# mdcu.net
KiCad netlist of a schematic drawn in Altium Designer
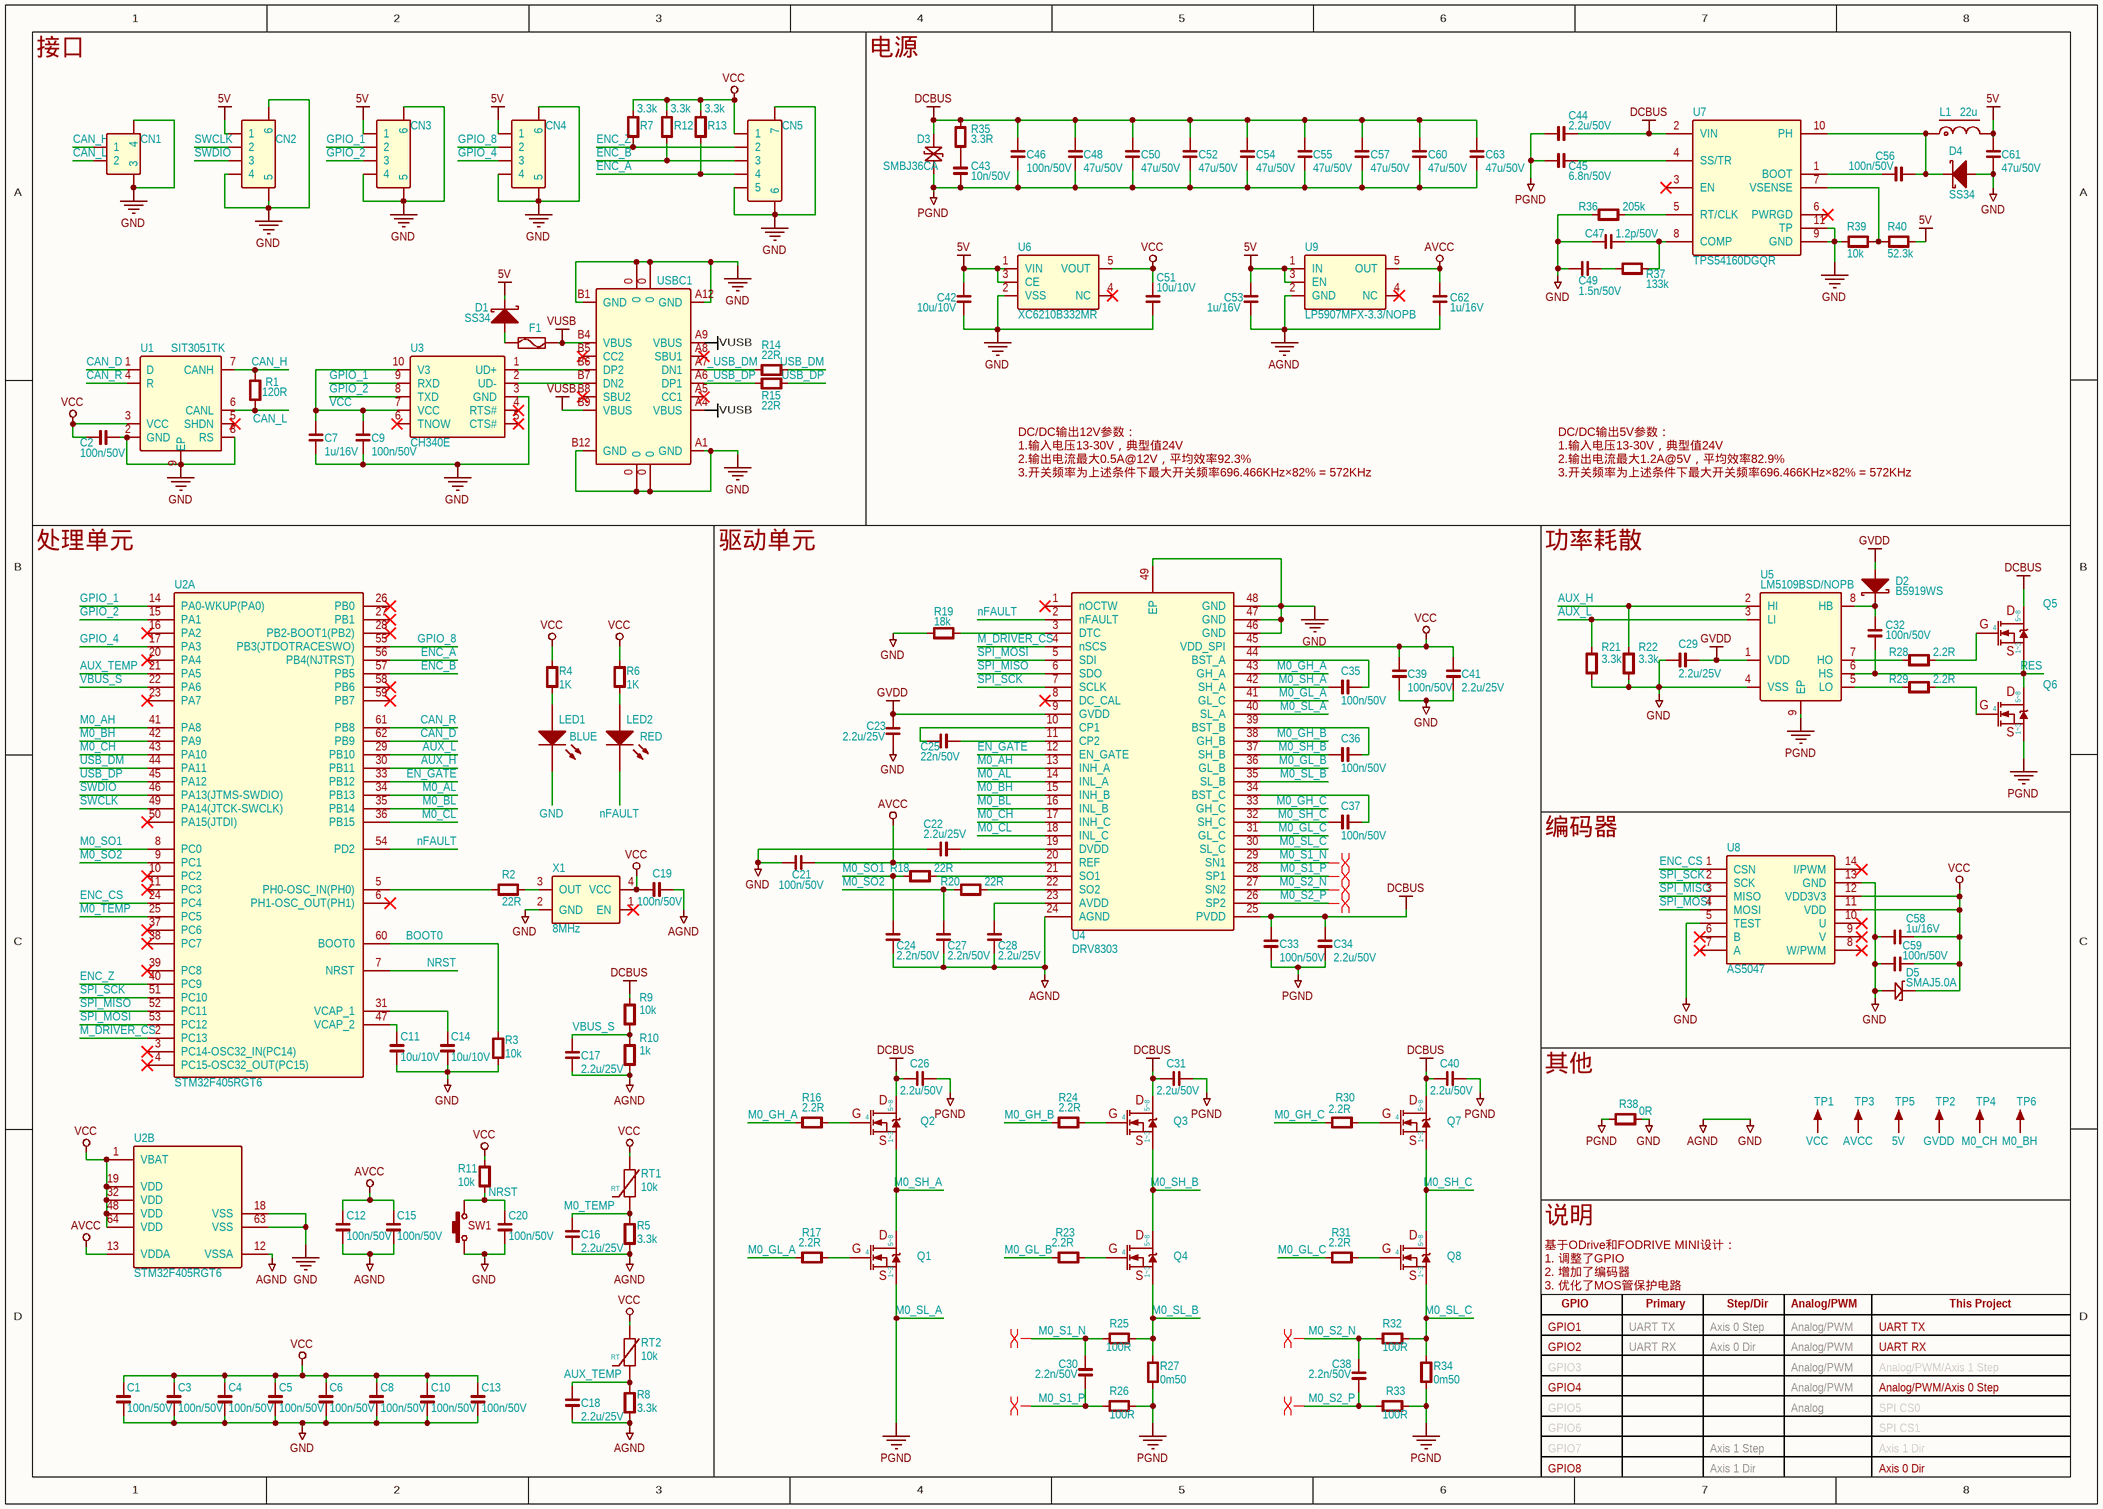
[diagram p0: mdcu.schdoc]

(export (version "E")
  (design (tool "Eeschema 10.0.6"))
  (components
    (comp (ref "C1")
      (value "100n/50V")
      (footprint "C0402_M")
      (description "贴片电容/MLCC电容")
      (libsource (lib "0.1 - 电阻-电容-电感-晶振-晶体-磁珠-电位器-法拉电容-馈通电容") (part "C"))
    )
    (comp (ref "C2")
      (value "100n/50V")
      (footprint "C0402_M")
      (description "贴片电容/MLCC电容")
      (libsource (lib "0.1 - 电阻-电容-电感-晶振-晶体-磁珠-电位器-法拉电容-馈通电容") (part "C"))
    )
    (comp (ref "C3")
      (value "100n/50V")
      (footprint "C0402_M")
      (description "贴片电容/MLCC电容")
      (libsource (lib "0.1 - 电阻-电容-电感-晶振-晶体-磁珠-电位器-法拉电容-馈通电容") (part "C"))
    )
    (comp (ref "C4")
      (value "100n/50V")
      (footprint "C0402_M")
      (description "贴片电容/MLCC电容")
      (libsource (lib "0.1 - 电阻-电容-电感-晶振-晶体-磁珠-电位器-法拉电容-馈通电容") (part "C"))
    )
    (comp (ref "C5")
      (value "100n/50V")
      (footprint "C0402_M")
      (description "贴片电容/MLCC电容")
      (libsource (lib "0.1 - 电阻-电容-电感-晶振-晶体-磁珠-电位器-法拉电容-馈通电容") (part "C"))
    )
    (comp (ref "C6")
      (value "100n/50V")
      (footprint "C0402_M")
      (description "贴片电容/MLCC电容")
      (libsource (lib "0.1 - 电阻-电容-电感-晶振-晶体-磁珠-电位器-法拉电容-馈通电容") (part "C"))
    )
    (comp (ref "C7")
      (value "1u/16V")
      (footprint "C0402_M")
      (description "贴片电容/MLCC电容")
      (libsource (lib "0.1 - 电阻-电容-电感-晶振-晶体-磁珠-电位器-法拉电容-馈通电容") (part "C"))
    )
    (comp (ref "C8")
      (value "100n/50V")
      (footprint "C0402_M")
      (description "贴片电容/MLCC电容")
      (libsource (lib "0.1 - 电阻-电容-电感-晶振-晶体-磁珠-电位器-法拉电容-馈通电容") (part "C"))
    )
    (comp (ref "C9")
      (value "100n/50V")
      (footprint "C0402_M")
      (description "贴片电容/MLCC电容")
      (libsource (lib "0.1 - 电阻-电容-电感-晶振-晶体-磁珠-电位器-法拉电容-馈通电容") (part "C"))
    )
    (comp (ref "C10")
      (value "100n/50V")
      (footprint "C0402_M")
      (description "贴片电容/MLCC电容")
      (libsource (lib "0.1 - 电阻-电容-电感-晶振-晶体-磁珠-电位器-法拉电容-馈通电容") (part "C"))
    )
    (comp (ref "C11")
      (value "10u/10V")
      (footprint "C0402_M")
      (description "贴片电容/MLCC电容")
      (libsource (lib "0.1 - 电阻-电容-电感-晶振-晶体-磁珠-电位器-法拉电容-馈通电容") (part "C"))
    )
    (comp (ref "C12")
      (value "100n/50V")
      (footprint "C0402_M")
      (description "贴片电容/MLCC电容")
      (libsource (lib "0.1 - 电阻-电容-电感-晶振-晶体-磁珠-电位器-法拉电容-馈通电容") (part "C"))
    )
    (comp (ref "C13")
      (value "100n/50V")
      (footprint "C0402_M")
      (description "贴片电容/MLCC电容")
      (libsource (lib "0.1 - 电阻-电容-电感-晶振-晶体-磁珠-电位器-法拉电容-馈通电容") (part "C"))
    )
    (comp (ref "C14")
      (value "10u/10V")
      (footprint "C0402_M")
      (description "贴片电容/MLCC电容")
      (libsource (lib "0.1 - 电阻-电容-电感-晶振-晶体-磁珠-电位器-法拉电容-馈通电容") (part "C"))
    )
    (comp (ref "C15")
      (value "100n/50V")
      (footprint "C0402_M")
      (description "贴片电容/MLCC电容")
      (libsource (lib "0.1 - 电阻-电容-电感-晶振-晶体-磁珠-电位器-法拉电容-馈通电容") (part "C"))
    )
    (comp (ref "C16")
      (value "2.2u/25V")
      (footprint "C0402_M")
      (description "贴片电容/MLCC电容")
      (libsource (lib "0.1 - 电阻-电容-电感-晶振-晶体-磁珠-电位器-法拉电容-馈通电容") (part "C"))
    )
    (comp (ref "C17")
      (value "2.2u/25V")
      (footprint "C0402_M")
      (description "贴片电容/MLCC电容")
      (libsource (lib "0.1 - 电阻-电容-电感-晶振-晶体-磁珠-电位器-法拉电容-馈通电容") (part "C"))
    )
    (comp (ref "C18")
      (value "2.2u/25V")
      (footprint "C0402_M")
      (description "贴片电容/MLCC电容")
      (libsource (lib "0.1 - 电阻-电容-电感-晶振-晶体-磁珠-电位器-法拉电容-馈通电容") (part "C"))
    )
    (comp (ref "C19")
      (value "100n/50V")
      (footprint "C0402_M")
      (description "贴片电容/MLCC电容")
      (libsource (lib "0.1 - 电阻-电容-电感-晶振-晶体-磁珠-电位器-法拉电容-馈通电容") (part "C"))
    )
    (comp (ref "C20")
      (value "100n/50V")
      (footprint "C0402_M")
      (description "贴片电容/MLCC电容")
      (libsource (lib "0.1 - 电阻-电容-电感-晶振-晶体-磁珠-电位器-法拉电容-馈通电容") (part "C"))
    )
    (comp (ref "C21")
      (value "100n/50V")
      (footprint "C0402_M")
      (description "贴片电容/MLCC电容")
      (libsource (lib "0.1 - 电阻-电容-电感-晶振-晶体-磁珠-电位器-法拉电容-馈通电容") (part "C"))
    )
    (comp (ref "C22")
      (value "2.2u/25V")
      (footprint "C0402_M")
      (description "贴片电容/MLCC电容")
      (libsource (lib "0.1 - 电阻-电容-电感-晶振-晶体-磁珠-电位器-法拉电容-馈通电容") (part "C"))
    )
    (comp (ref "C23")
      (value "2.2u/25V")
      (footprint "C0402_M")
      (description "贴片电容/MLCC电容")
      (libsource (lib "0.1 - 电阻-电容-电感-晶振-晶体-磁珠-电位器-法拉电容-馈通电容") (part "C"))
    )
    (comp (ref "C24")
      (value "2.2n/50V")
      (footprint "C0402_M")
      (description "贴片电容/MLCC电容")
      (libsource (lib "0.1 - 电阻-电容-电感-晶振-晶体-磁珠-电位器-法拉电容-馈通电容") (part "C"))
    )
    (comp (ref "C25")
      (value "22n/50V")
      (footprint "C0402_M")
      (description "贴片电容/MLCC电容")
      (libsource (lib "0.1 - 电阻-电容-电感-晶振-晶体-磁珠-电位器-法拉电容-馈通电容") (part "C"))
    )
    (comp (ref "C26")
      (value "2.2u/50V")
      (footprint "C0603_M")
      (description "贴片电容/MLCC电容")
      (libsource (lib "0.1 - 电阻-电容-电感-晶振-晶体-磁珠-电位器-法拉电容-馈通电容") (part "C"))
    )
    (comp (ref "C27")
      (value "2.2n/50V")
      (footprint "C0402_M")
      (description "贴片电容/MLCC电容")
      (libsource (lib "0.1 - 电阻-电容-电感-晶振-晶体-磁珠-电位器-法拉电容-馈通电容") (part "C"))
    )
    (comp (ref "C28")
      (value "2.2u/25V")
      (footprint "C0402_M")
      (description "贴片电容/MLCC电容")
      (libsource (lib "0.1 - 电阻-电容-电感-晶振-晶体-磁珠-电位器-法拉电容-馈通电容") (part "C"))
    )
    (comp (ref "C29")
      (value "2.2u/25V")
      (footprint "C0402_M")
      (description "贴片电容/MLCC电容")
      (libsource (lib "0.1 - 电阻-电容-电感-晶振-晶体-磁珠-电位器-法拉电容-馈通电容") (part "C"))
    )
    (comp (ref "C30")
      (value "2.2n/50V")
      (footprint "C0402_M")
      (description "贴片电容/MLCC电容")
      (libsource (lib "0.1 - 电阻-电容-电感-晶振-晶体-磁珠-电位器-法拉电容-馈通电容") (part "C"))
    )
    (comp (ref "C31")
      (value "2.2u/50V")
      (footprint "C0603_M")
      (description "贴片电容/MLCC电容")
      (libsource (lib "0.1 - 电阻-电容-电感-晶振-晶体-磁珠-电位器-法拉电容-馈通电容") (part "C"))
    )
    (comp (ref "C32")
      (value "100n/50V")
      (footprint "C0402_M")
      (description "贴片电容/MLCC电容")
      (libsource (lib "0.1 - 电阻-电容-电感-晶振-晶体-磁珠-电位器-法拉电容-馈通电容") (part "C"))
    )
    (comp (ref "C33")
      (value "100n/50V")
      (footprint "C0402_M")
      (description "贴片电容/MLCC电容")
      (libsource (lib "0.1 - 电阻-电容-电感-晶振-晶体-磁珠-电位器-法拉电容-馈通电容") (part "C"))
    )
    (comp (ref "C34")
      (value "2.2u/50V")
      (footprint "C0603_M")
      (description "贴片电容/MLCC电容")
      (libsource (lib "0.1 - 电阻-电容-电感-晶振-晶体-磁珠-电位器-法拉电容-馈通电容") (part "C"))
    )
    (comp (ref "C35")
      (value "100n/50V")
      (footprint "C0402_M")
      (description "贴片电容/MLCC电容")
      (libsource (lib "0.1 - 电阻-电容-电感-晶振-晶体-磁珠-电位器-法拉电容-馈通电容") (part "C"))
    )
    (comp (ref "C36")
      (value "100n/50V")
      (footprint "C0402_M")
      (description "贴片电容/MLCC电容")
      (libsource (lib "0.1 - 电阻-电容-电感-晶振-晶体-磁珠-电位器-法拉电容-馈通电容") (part "C"))
    )
    (comp (ref "C37")
      (value "100n/50V")
      (footprint "C0402_M")
      (description "贴片电容/MLCC电容")
      (libsource (lib "0.1 - 电阻-电容-电感-晶振-晶体-磁珠-电位器-法拉电容-馈通电容") (part "C"))
    )
    (comp (ref "C38")
      (value "2.2n/50V")
      (footprint "C0402_M")
      (description "贴片电容/MLCC电容")
      (libsource (lib "0.1 - 电阻-电容-电感-晶振-晶体-磁珠-电位器-法拉电容-馈通电容") (part "C"))
    )
    (comp (ref "C39")
      (value "100n/50V")
      (footprint "C0402_M")
      (description "贴片电容/MLCC电容")
      (libsource (lib "0.1 - 电阻-电容-电感-晶振-晶体-磁珠-电位器-法拉电容-馈通电容") (part "C"))
    )
    (comp (ref "C40")
      (value "2.2u/50V")
      (footprint "C0603_M")
      (description "贴片电容/MLCC电容")
      (libsource (lib "0.1 - 电阻-电容-电感-晶振-晶体-磁珠-电位器-法拉电容-馈通电容") (part "C"))
    )
    (comp (ref "C41")
      (value "2.2u/25V")
      (footprint "C0402_M")
      (description "贴片电容/MLCC电容")
      (libsource (lib "0.1 - 电阻-电容-电感-晶振-晶体-磁珠-电位器-法拉电容-馈通电容") (part "C"))
    )
    (comp (ref "C42")
      (value "10u/10V")
      (footprint "C0402_M")
      (description "贴片电容/MLCC电容")
      (libsource (lib "0.1 - 电阻-电容-电感-晶振-晶体-磁珠-电位器-法拉电容-馈通电容") (part "C"))
    )
    (comp (ref "C43")
      (value "10n/50V")
      (footprint "C0402_M")
      (description "贴片电容/MLCC电容")
      (libsource (lib "0.1 - 电阻-电容-电感-晶振-晶体-磁珠-电位器-法拉电容-馈通电容") (part "C"))
    )
    (comp (ref "C44")
      (value "2.2u/50V")
      (footprint "C0603_M")
      (description "贴片电容/MLCC电容")
      (libsource (lib "0.1 - 电阻-电容-电感-晶振-晶体-磁珠-电位器-法拉电容-馈通电容") (part "C"))
    )
    (comp (ref "C45")
      (value "6.8n/50V")
      (footprint "C0402_M")
      (description "贴片电容/MLCC电容")
      (libsource (lib "0.1 - 电阻-电容-电感-晶振-晶体-磁珠-电位器-法拉电容-馈通电容") (part "C"))
    )
    (comp (ref "C46")
      (value "100n/50V")
      (footprint "C0402_M")
      (description "贴片电容/MLCC电容")
      (libsource (lib "0.1 - 电阻-电容-电感-晶振-晶体-磁珠-电位器-法拉电容-馈通电容") (part "C"))
    )
    (comp (ref "C47")
      (value "1.2p/50V")
      (footprint "C0402_M")
      (description "贴片电容/MLCC电容")
      (libsource (lib "0.1 - 电阻-电容-电感-晶振-晶体-磁珠-电位器-法拉电容-馈通电容") (part "C"))
    )
    (comp (ref "C48")
      (value "47u/50V")
      (footprint "C1812_M")
      (description "贴片电容/MLCC电容")
      (libsource (lib "0.1 - 电阻-电容-电感-晶振-晶体-磁珠-电位器-法拉电容-馈通电容") (part "C"))
    )
    (comp (ref "C49")
      (value "1.5n/50V")
      (footprint "C0402_M")
      (description "贴片电容/MLCC电容")
      (libsource (lib "0.1 - 电阻-电容-电感-晶振-晶体-磁珠-电位器-法拉电容-馈通电容") (part "C"))
    )
    (comp (ref "C50")
      (value "47u/50V")
      (footprint "C1812_M")
      (description "贴片电容/MLCC电容")
      (libsource (lib "0.1 - 电阻-电容-电感-晶振-晶体-磁珠-电位器-法拉电容-馈通电容") (part "C"))
    )
    (comp (ref "C51")
      (value "10u/10V")
      (footprint "C0402_M")
      (description "贴片电容/MLCC电容")
      (libsource (lib "0.1 - 电阻-电容-电感-晶振-晶体-磁珠-电位器-法拉电容-馈通电容") (part "C"))
    )
    (comp (ref "C52")
      (value "47u/50V")
      (footprint "C1812_M")
      (description "贴片电容/MLCC电容")
      (libsource (lib "0.1 - 电阻-电容-电感-晶振-晶体-磁珠-电位器-法拉电容-馈通电容") (part "C"))
    )
    (comp (ref "C53")
      (value "1u/16V")
      (footprint "C0402_M")
      (description "贴片电容/MLCC电容")
      (libsource (lib "0.1 - 电阻-电容-电感-晶振-晶体-磁珠-电位器-法拉电容-馈通电容") (part "C"))
    )
    (comp (ref "C54")
      (value "47u/50V")
      (footprint "C1812_M")
      (description "贴片电容/MLCC电容")
      (libsource (lib "0.1 - 电阻-电容-电感-晶振-晶体-磁珠-电位器-法拉电容-馈通电容") (part "C"))
    )
    (comp (ref "C55")
      (value "47u/50V")
      (footprint "C1812_M")
      (description "贴片电容/MLCC电容")
      (libsource (lib "0.1 - 电阻-电容-电感-晶振-晶体-磁珠-电位器-法拉电容-馈通电容") (part "C"))
    )
    (comp (ref "C56")
      (value "100n/50V")
      (footprint "C0402_M")
      (description "贴片电容/MLCC电容")
      (libsource (lib "0.1 - 电阻-电容-电感-晶振-晶体-磁珠-电位器-法拉电容-馈通电容") (part "C"))
    )
    (comp (ref "C57")
      (value "47u/50V")
      (footprint "C1812_M")
      (description "贴片电容/MLCC电容")
      (libsource (lib "0.1 - 电阻-电容-电感-晶振-晶体-磁珠-电位器-法拉电容-馈通电容") (part "C"))
    )
    (comp (ref "C58")
      (value "1u/16V")
      (footprint "C0402_M")
      (description "贴片电容/MLCC电容")
      (libsource (lib "0.1 - 电阻-电容-电感-晶振-晶体-磁珠-电位器-法拉电容-馈通电容") (part "C"))
    )
    (comp (ref "C59")
      (value "100n/50V")
      (footprint "C0402_M")
      (description "贴片电容/MLCC电容")
      (libsource (lib "0.1 - 电阻-电容-电感-晶振-晶体-磁珠-电位器-法拉电容-馈通电容") (part "C"))
    )
    (comp (ref "C60")
      (value "47u/50V")
      (footprint "C1812_M")
      (description "贴片电容/MLCC电容")
      (libsource (lib "0.1 - 电阻-电容-电感-晶振-晶体-磁珠-电位器-法拉电容-馈通电容") (part "C"))
    )
    (comp (ref "C61")
      (value "47u/50V")
      (footprint "C1812_M")
      (description "贴片电容/MLCC电容")
      (libsource (lib "0.1 - 电阻-电容-电感-晶振-晶体-磁珠-电位器-法拉电容-馈通电容") (part "C"))
    )
    (comp (ref "C62")
      (value "1u/16V")
      (footprint "C0402_M")
      (description "贴片电容/MLCC电容")
      (libsource (lib "0.1 - 电阻-电容-电感-晶振-晶体-磁珠-电位器-法拉电容-馈通电容") (part "C"))
    )
    (comp (ref "C63")
      (value "47u/50V")
      (footprint "C1812_M")
      (description "贴片电容/MLCC电容")
      (libsource (lib "0.1 - 电阻-电容-电感-晶振-晶体-磁珠-电位器-法拉电容-馈通电容") (part "C"))
    )
    (comp (ref "CN1")
      (value "CON-2P")
      (footprint "SH1.0-WT-2P")
      (description "2P连接器")
      (libsource (lib "5.0 - 1.00mm连接器(FPC1.0_SH1.0_1.0排针排母)") (part "Header 2"))
    )
    (comp (ref "CN2")
      (value "CON-4P")
      (footprint "SH1.0-WT-4P")
      (description "4P连接器")
      (libsource (lib "5.0 - 1.00mm连接器(FPC1.0_SH1.0_1.0排针排母)") (part "Header 4"))
    )
    (comp (ref "CN3")
      (value "CON-4P")
      (footprint "SH1.0-WT-4P")
      (description "4P连接器")
      (libsource (lib "5.0 - 1.00mm连接器(FPC1.0_SH1.0_1.0排针排母)") (part "Header 4"))
    )
    (comp (ref "CN4")
      (value "CON-4P")
      (footprint "SH1.0-WT-4P")
      (description "4P连接器")
      (libsource (lib "5.0 - 1.00mm连接器(FPC1.0_SH1.0_1.0排针排母)") (part "Header 4"))
    )
    (comp (ref "CN5")
      (value "CON-5P")
      (footprint "SH1.0-WT-5P")
      (description "5P连接器")
      (libsource (lib "5.0 - 1.00mm连接器(FPC1.0_SH1.0_1.0排针排母)") (part "Header 5"))
    )
    (comp (ref "D1")
      (value "SS34")
      (footprint "SMA")
      (description "肖特基二极管")
      (libsource (lib "0.2 - 二极管-TVS-ESD-整流桥-放电管") (part "SS34"))
    )
    (comp (ref "D2")
      (value "B5919WS")
      (footprint "SOD-323")
      (description "肖特基二极管")
      (libsource (lib "0.2 - 二极管-TVS-ESD-整流桥-放电管") (part "B5819"))
    )
    (comp (ref "D3")
      (value "SMBJ36CA")
      (footprint "SMB-NS")
      (description "瞬态电压抑制二极管-双向")
      (libsource (lib "0.2 - 二极管-TVS-ESD-整流桥-放电管") (part "DR_CA"))
    )
    (comp (ref "D4")
      (value "SS34")
      (footprint "SMA")
      (description "肖特基二极管")
      (libsource (lib "0.2 - 二极管-TVS-ESD-整流桥-放电管") (part "SS34"))
    )
    (comp (ref "D5")
      (value "SMAJ5.0A")
      (footprint "SMA")
      (description "瞬态电压抑制二极管-单向")
      (libsource (lib "0.2 - 二极管-TVS-ESD-整流桥-放电管") (part "DR"))
    )
    (comp (ref "F1")
      (value "FSMD012-1206-R")
      (footprint "FU 1206")
      (description "PPTC自恢复保险丝")
      (libsource (lib "0.5 - 按键_开关_蜂鸣器_保险丝_电池_测试点_Mark点_铜柱") (part "FU-PPTC"))
    )
    (comp (ref "L1")
      (value "22u")
      (footprint "CDRH73")
      (description "CDRH功率屏蔽电感")
      (libsource (lib "0.1 - 电阻-电容-电感-晶振-晶体-磁珠-电位器-法拉电容-馈通电容") (part "L-CDRH"))
    )
    (comp (ref "LED1")
      (value "BLUE")
      (footprint "LED0603_B")
      (description "贴片LED")
      (libsource (lib "0.3 - LED发光二极管-IR二极管_接收管-光耦") (part "LED"))
    )
    (comp (ref "LED2")
      (value "RED")
      (footprint "LED0603_R")
      (description "贴片LED")
      (libsource (lib "0.3 - LED发光二极管-IR二极管_接收管-光耦") (part "LED"))
    )
    (comp (ref "Q1")
      (value "MOSFET-1N-POWER")
      (footprint "PDFN-8-L6-W5-P1.27-3PAD")
      (description "N沟道功率型场效应管")
      (fields (field (name "MF") "ON Semiconductor") (field (name "MP") "NTMFS4935NT1G"))
      (libsource (lib "0.4 - 三极管-场效应管-可控硅") (part "MOSFET-1N-POWER"))
    )
    (comp (ref "Q2")
      (value "MOSFET-1N-POWER")
      (footprint "PDFN-8-L6-W5-P1.27-3PAD")
      (description "N沟道功率型场效应管")
      (fields (field (name "MF") "ON Semiconductor") (field (name "MP") "NTMFS4935NT1G"))
      (libsource (lib "0.4 - 三极管-场效应管-可控硅") (part "MOSFET-1N-POWER"))
    )
    (comp (ref "Q3")
      (value "MOSFET-1N-POWER")
      (footprint "PDFN-8-L6-W5-P1.27-3PAD")
      (description "N沟道功率型场效应管")
      (fields (field (name "MF") "ON Semiconductor") (field (name "MP") "NTMFS4935NT1G"))
      (libsource (lib "0.4 - 三极管-场效应管-可控硅") (part "MOSFET-1N-POWER"))
    )
    (comp (ref "Q4")
      (value "MOSFET-1N-POWER")
      (footprint "PDFN-8-L6-W5-P1.27-3PAD")
      (description "N沟道功率型场效应管")
      (fields (field (name "MF") "ON Semiconductor") (field (name "MP") "NTMFS4935NT1G"))
      (libsource (lib "0.4 - 三极管-场效应管-可控硅") (part "MOSFET-1N-POWER"))
    )
    (comp (ref "Q5")
      (value "MOSFET-1N-POWER")
      (footprint "PDFN-8-L6-W5-P1.27-3PAD")
      (description "N沟道功率型场效应管")
      (fields (field (name "MF") "ON Semiconductor") (field (name "MP") "NTMFS4935NT1G"))
      (libsource (lib "0.4 - 三极管-场效应管-可控硅") (part "MOSFET-1N-POWER"))
    )
    (comp (ref "Q6")
      (value "MOSFET-1N-POWER")
      (footprint "PDFN-8-L6-W5-P1.27-3PAD")
      (description "N沟道功率型场效应管")
      (fields (field (name "MF") "ON Semiconductor") (field (name "MP") "NTMFS4935NT1G"))
      (libsource (lib "0.4 - 三极管-场效应管-可控硅") (part "MOSFET-1N-POWER"))
    )
    (comp (ref "Q7")
      (value "MOSFET-1N-POWER")
      (footprint "PDFN-8-L6-W5-P1.27-3PAD")
      (description "N沟道功率型场效应管")
      (fields (field (name "MF") "ON Semiconductor") (field (name "MP") "NTMFS4935NT1G"))
      (libsource (lib "0.4 - 三极管-场效应管-可控硅") (part "MOSFET-1N-POWER"))
    )
    (comp (ref "Q8")
      (value "MOSFET-1N-POWER")
      (footprint "PDFN-8-L6-W5-P1.27-3PAD")
      (description "N沟道功率型场效应管")
      (fields (field (name "MF") "ON Semiconductor") (field (name "MP") "NTMFS4935NT1G"))
      (libsource (lib "0.4 - 三极管-场效应管-可控硅") (part "MOSFET-1N-POWER"))
    )
    (comp (ref "R1")
      (value "120R")
      (footprint "R0402_M")
      (description "贴片电阻")
      (libsource (lib "0.1 - 电阻-电容-电感-晶振-晶体-磁珠-电位器-法拉电容-馈通电容") (part "R"))
    )
    (comp (ref "R2")
      (value "22R")
      (footprint "R0402_M")
      (description "贴片电阻")
      (libsource (lib "0.1 - 电阻-电容-电感-晶振-晶体-磁珠-电位器-法拉电容-馈通电容") (part "R"))
    )
    (comp (ref "R3")
      (value "10k")
      (footprint "R0402_M")
      (description "贴片电阻")
      (libsource (lib "0.1 - 电阻-电容-电感-晶振-晶体-磁珠-电位器-法拉电容-馈通电容") (part "R"))
    )
    (comp (ref "R4")
      (value "1K")
      (footprint "R0402_M")
      (description "贴片电阻")
      (libsource (lib "0.1 - 电阻-电容-电感-晶振-晶体-磁珠-电位器-法拉电容-馈通电容") (part "R"))
    )
    (comp (ref "R5")
      (value "3.3k")
      (footprint "R0402_M")
      (description "贴片电阻")
      (libsource (lib "0.1 - 电阻-电容-电感-晶振-晶体-磁珠-电位器-法拉电容-馈通电容") (part "R"))
    )
    (comp (ref "R6")
      (value "1K")
      (footprint "R0402_M")
      (description "贴片电阻")
      (libsource (lib "0.1 - 电阻-电容-电感-晶振-晶体-磁珠-电位器-法拉电容-馈通电容") (part "R"))
    )
    (comp (ref "R7")
      (value "3.3k")
      (footprint "R0402_M")
      (description "贴片电阻")
      (libsource (lib "0.1 - 电阻-电容-电感-晶振-晶体-磁珠-电位器-法拉电容-馈通电容") (part "R"))
    )
    (comp (ref "R8")
      (value "3.3k")
      (footprint "R0402_M")
      (description "贴片电阻")
      (libsource (lib "0.1 - 电阻-电容-电感-晶振-晶体-磁珠-电位器-法拉电容-馈通电容") (part "R"))
    )
    (comp (ref "R9")
      (value "10k")
      (footprint "R0402_M")
      (description "贴片电阻")
      (libsource (lib "0.1 - 电阻-电容-电感-晶振-晶体-磁珠-电位器-法拉电容-馈通电容") (part "R"))
    )
    (comp (ref "R10")
      (value "1k")
      (footprint "R0402_M")
      (description "贴片电阻")
      (libsource (lib "0.1 - 电阻-电容-电感-晶振-晶体-磁珠-电位器-法拉电容-馈通电容") (part "R"))
    )
    (comp (ref "R11")
      (value "10k")
      (footprint "R0402_M")
      (description "贴片电阻")
      (libsource (lib "0.1 - 电阻-电容-电感-晶振-晶体-磁珠-电位器-法拉电容-馈通电容") (part "R"))
    )
    (comp (ref "R12")
      (value "3.3k")
      (footprint "R0402_M")
      (description "贴片电阻")
      (libsource (lib "0.1 - 电阻-电容-电感-晶振-晶体-磁珠-电位器-法拉电容-馈通电容") (part "R"))
    )
    (comp (ref "R13")
      (value "3.3k")
      (footprint "R0402_M")
      (description "贴片电阻")
      (libsource (lib "0.1 - 电阻-电容-电感-晶振-晶体-磁珠-电位器-法拉电容-馈通电容") (part "R"))
    )
    (comp (ref "R14")
      (value "22R")
      (footprint "R0402_M")
      (description "贴片电阻")
      (libsource (lib "0.1 - 电阻-电容-电感-晶振-晶体-磁珠-电位器-法拉电容-馈通电容") (part "R"))
    )
    (comp (ref "R15")
      (value "22R")
      (footprint "R0402_M")
      (description "贴片电阻")
      (libsource (lib "0.1 - 电阻-电容-电感-晶振-晶体-磁珠-电位器-法拉电容-馈通电容") (part "R"))
    )
    (comp (ref "R16")
      (value "2.2R")
      (footprint "R0402_M")
      (description "贴片电阻")
      (libsource (lib "0.1 - 电阻-电容-电感-晶振-晶体-磁珠-电位器-法拉电容-馈通电容") (part "R"))
    )
    (comp (ref "R17")
      (value "2.2R")
      (footprint "R0402_M")
      (description "贴片电阻")
      (libsource (lib "0.1 - 电阻-电容-电感-晶振-晶体-磁珠-电位器-法拉电容-馈通电容") (part "R"))
    )
    (comp (ref "R18")
      (value "22R")
      (footprint "R0402_M")
      (description "贴片电阻")
      (libsource (lib "0.1 - 电阻-电容-电感-晶振-晶体-磁珠-电位器-法拉电容-馈通电容") (part "R"))
    )
    (comp (ref "R19")
      (value "18k")
      (footprint "R0402_M")
      (description "贴片电阻")
      (libsource (lib "0.1 - 电阻-电容-电感-晶振-晶体-磁珠-电位器-法拉电容-馈通电容") (part "R"))
    )
    (comp (ref "R20")
      (value "22R")
      (footprint "R0402_M")
      (description "贴片电阻")
      (libsource (lib "0.1 - 电阻-电容-电感-晶振-晶体-磁珠-电位器-法拉电容-馈通电容") (part "R"))
    )
    (comp (ref "R21")
      (value "3.3k")
      (footprint "R0402_M")
      (description "贴片电阻")
      (libsource (lib "0.1 - 电阻-电容-电感-晶振-晶体-磁珠-电位器-法拉电容-馈通电容") (part "R"))
    )
    (comp (ref "R22")
      (value "3.3k")
      (footprint "R0402_M")
      (description "贴片电阻")
      (libsource (lib "0.1 - 电阻-电容-电感-晶振-晶体-磁珠-电位器-法拉电容-馈通电容") (part "R"))
    )
    (comp (ref "R23")
      (value "2.2R")
      (footprint "R0402_M")
      (description "贴片电阻")
      (libsource (lib "0.1 - 电阻-电容-电感-晶振-晶体-磁珠-电位器-法拉电容-馈通电容") (part "R"))
    )
    (comp (ref "R24")
      (value "2.2R")
      (footprint "R0402_M")
      (description "贴片电阻")
      (libsource (lib "0.1 - 电阻-电容-电感-晶振-晶体-磁珠-电位器-法拉电容-馈通电容") (part "R"))
    )
    (comp (ref "R25")
      (value "100R")
      (footprint "R0402_M")
      (description "贴片电阻")
      (libsource (lib "0.1 - 电阻-电容-电感-晶振-晶体-磁珠-电位器-法拉电容-馈通电容") (part "R"))
    )
    (comp (ref "R26")
      (value "100R")
      (footprint "R0402_M")
      (description "贴片电阻")
      (libsource (lib "0.1 - 电阻-电容-电感-晶振-晶体-磁珠-电位器-法拉电容-馈通电容") (part "R"))
    )
    (comp (ref "R27")
      (value "0m50")
      (footprint "R2512-HP_M")
      (description "贴片精密电阻")
      (libsource (lib "0.1 - 电阻-电容-电感-晶振-晶体-磁珠-电位器-法拉电容-馈通电容") (part "R-High Precision"))
    )
    (comp (ref "R28")
      (value "2.2R")
      (footprint "R0402_M")
      (description "贴片电阻")
      (libsource (lib "0.1 - 电阻-电容-电感-晶振-晶体-磁珠-电位器-法拉电容-馈通电容") (part "R"))
    )
    (comp (ref "R29")
      (value "2.2R")
      (footprint "R0402_M")
      (description "贴片电阻")
      (libsource (lib "0.1 - 电阻-电容-电感-晶振-晶体-磁珠-电位器-法拉电容-馈通电容") (part "R"))
    )
    (comp (ref "R30")
      (value "2.2R")
      (footprint "R0402_M")
      (description "贴片电阻")
      (libsource (lib "0.1 - 电阻-电容-电感-晶振-晶体-磁珠-电位器-法拉电容-馈通电容") (part "R"))
    )
    (comp (ref "R31")
      (value "2.2R")
      (footprint "R0402_M")
      (description "贴片电阻")
      (libsource (lib "0.1 - 电阻-电容-电感-晶振-晶体-磁珠-电位器-法拉电容-馈通电容") (part "R"))
    )
    (comp (ref "R32")
      (value "100R")
      (footprint "R0402_M")
      (description "贴片电阻")
      (libsource (lib "0.1 - 电阻-电容-电感-晶振-晶体-磁珠-电位器-法拉电容-馈通电容") (part "R"))
    )
    (comp (ref "R33")
      (value "100R")
      (footprint "R0402_M")
      (description "贴片电阻")
      (libsource (lib "0.1 - 电阻-电容-电感-晶振-晶体-磁珠-电位器-法拉电容-馈通电容") (part "R"))
    )
    (comp (ref "R34")
      (value "0m50")
      (footprint "R2512-HP_M")
      (description "贴片精密电阻")
      (libsource (lib "0.1 - 电阻-电容-电感-晶振-晶体-磁珠-电位器-法拉电容-馈通电容") (part "R-High Precision"))
    )
    (comp (ref "R35")
      (value "3.3R")
      (footprint "R0402_M")
      (description "贴片电阻")
      (libsource (lib "0.1 - 电阻-电容-电感-晶振-晶体-磁珠-电位器-法拉电容-馈通电容") (part "R"))
    )
    (comp (ref "R36")
      (value "205k")
      (footprint "R0402_M")
      (description "贴片电阻")
      (libsource (lib "0.1 - 电阻-电容-电感-晶振-晶体-磁珠-电位器-法拉电容-馈通电容") (part "R"))
    )
    (comp (ref "R37")
      (value "133k")
      (footprint "R0402_M")
      (description "贴片电阻")
      (libsource (lib "0.1 - 电阻-电容-电感-晶振-晶体-磁珠-电位器-法拉电容-馈通电容") (part "R"))
    )
    (comp (ref "R38")
      (value "0R")
      (footprint "R0402_M")
      (description "贴片电阻")
      (libsource (lib "0.1 - 电阻-电容-电感-晶振-晶体-磁珠-电位器-法拉电容-馈通电容") (part "R"))
    )
    (comp (ref "R39")
      (value "10k")
      (footprint "R0402_M")
      (description "贴片电阻")
      (libsource (lib "0.1 - 电阻-电容-电感-晶振-晶体-磁珠-电位器-法拉电容-馈通电容") (part "R"))
    )
    (comp (ref "R40")
      (value "52.3k")
      (footprint "R0402_M")
      (description "贴片电阻")
      (libsource (lib "0.1 - 电阻-电容-电感-晶振-晶体-磁珠-电位器-法拉电容-馈通电容") (part "R"))
    )
    (comp (ref "RT1")
      (value "10k")
      (footprint "R0402-HP_M")
      (description "热敏电阻")
      (libsource (lib "0.1 - 电阻-电容-电感-晶振-晶体-磁珠-电位器-法拉电容-馈通电容") (part "RT"))
    )
    (comp (ref "RT2")
      (value "10k")
      (footprint "R0402-HP_M")
      (description "热敏电阻")
      (libsource (lib "0.1 - 电阻-电容-电感-晶振-晶体-磁珠-电位器-法拉电容-馈通电容") (part "RT"))
    )
    (comp (ref "SW1")
      (value "3x6x5")
      (footprint "SW SMD-3*4*2-180")
      (description "微动开关")
      (libsource (lib "0.5 - 按键_开关_蜂鸣器_保险丝_电池_测试点_Mark点_铜柱") (part "SW-PB"))
    )
    (comp (ref "TP1")
      (value "VCC")
      (footprint "TEST 1")
      (description "测试点")
      (libsource (lib "0.5 - 按键_开关_蜂鸣器_保险丝_电池_测试点_Mark点_铜柱") (part "TEST"))
    )
    (comp (ref "TP2")
      (value "GVDD")
      (footprint "TEST 1")
      (description "测试点")
      (libsource (lib "0.5 - 按键_开关_蜂鸣器_保险丝_电池_测试点_Mark点_铜柱") (part "TEST"))
    )
    (comp (ref "TP3")
      (value "AVCC")
      (footprint "TEST 1")
      (description "测试点")
      (libsource (lib "0.5 - 按键_开关_蜂鸣器_保险丝_电池_测试点_Mark点_铜柱") (part "TEST"))
    )
    (comp (ref "TP4")
      (value "M0_CH")
      (footprint "TEST 1")
      (description "测试点")
      (libsource (lib "0.5 - 按键_开关_蜂鸣器_保险丝_电池_测试点_Mark点_铜柱") (part "TEST"))
    )
    (comp (ref "TP5")
      (value "5V")
      (footprint "TEST 1")
      (description "测试点")
      (libsource (lib "0.5 - 按键_开关_蜂鸣器_保险丝_电池_测试点_Mark点_铜柱") (part "TEST"))
    )
    (comp (ref "TP6")
      (value "M0_BH")
      (footprint "TEST 1")
      (description "测试点")
      (libsource (lib "0.5 - 按键_开关_蜂鸣器_保险丝_电池_测试点_Mark点_铜柱") (part "TEST"))
    )
    (comp (ref "U1")
      (value "SIT3051TK")
      (footprint "DFN-8_L3.0-W3.0-P0.65-BL-EP-M")
      (description "CAN芯片")
      (libsource (lib "0.8 - 常见芯片") (part "SIT3051TK"))
    )
    (comp (ref "U2")
      (value "STM32F405RGT6")
      (footprint "TQFP64 10x10_M")
      (fields (field (name "BOM_SUPPLIER PART") "C15742") (field (name "SUBPART_NO") "1"))
      (libsource (lib "2.7 - STM32 F4系列单片机") (part "STM32F405RGT6_V2"))
    )
    (comp (ref "U3")
      (value "CH340E")
      (footprint "MSOP10_L")
      (description "USB转串口芯片，内置时钟")
      (libsource (lib "0.8 - 常见芯片") (part "CH340E"))
    )
    (comp (ref "U4")
      (value "DRV8303")
      (footprint "HTSSOP-48_L12.5-W6.1-P0.50-M")
      (description "三相电机驱动应用的栅极驱动\r\n器")
      (fields (field (name "BOM_SUPPLIER PART") "C91880") (field (name "CONTRIBUTOR") "矛盾聚合体"))
      (libsource (lib "0.8 - 常见芯片") (part "DRV8303"))
    )
    (comp (ref "U5")
      (value "LM5109BSD/NOPB")
      (footprint "WSON-8_L4.0-W4.0-P0.80-TL-EP")
      (description "USB转串口芯片，内置时钟")
      (libsource (lib "0.8 - 常见芯片") (part "LM5109"))
    )
    (comp (ref "U6")
      (value "XC6210B332MR")
      (footprint "SOT23-5L")
      (description "LDO 0.9A/3.3V")
      (libsource (lib "0.7 - 电源类芯片") (part "XC6210"))
    )
    (comp (ref "U7")
      (value "TPS54160DGQR")
      (footprint "MSOP10-L3.0-W3.0-P0.50-EP")
      (description "DC-DC 1.5A/60V 降压转换器")
      (libsource (lib "0.7 - 电源类芯片") (part "TPS54160DGQR"))
    )
    (comp (ref "U8")
      (value "AS5047")
      (footprint "TSSOP14_M")
      (description "AMS公司14位磁编码器")
      (fields (field (name "版权归属") "封装库来自淘宝 ID：黄晶宝石"))
      (libsource (lib "0.8 - 常见芯片") (part "AS5047"))
    )
    (comp (ref "U9")
      (value "LP5907MFX-3.3/NOPB")
      (footprint "SOT23-5L")
      (description "LDO 0.25A/3.3V 90dB@(100Hz),60dB@(100kHz)")
      (libsource (lib "0.7 - 电源类芯片") (part "LP5907"))
    )
    (comp (ref "USBC1")
      (value "TYPE-C 2.0 -16P")
      (footprint "USB-C-SMD_16P")
      (description "USB2.0_Type-C_16Pin母座")
      (libsource (lib "0.6 - 电源_音频_USB Type-C_HDMI_XT60_5557_D-SUB_RJ45_SD-TF_SIM插座") (part "USB2.0_Type-C_16Pin"))
    )
    (comp (ref "X1")
      (value "8MHz")
      (footprint "OSC-2025-4P")
      (description "4脚有源晶振(振荡器)")
      (libsource (lib "0.1 - 电阻-电容-电感-晶振-晶体-磁珠-电位器-法拉电容-馈通电容") (part "XTAL-ACT-4P"))
    )
  )
  (nets
    (net (code "1") (name "/AUX_H") (class "Default")
      (node (ref "R22") (pin "1") (pinfunction "1_1") (pintype "passive"))
      (node (ref "U2") (pin "30") (pinfunction "PB11_30") (pintype "passive"))
      (node (ref "U5") (pin "2") (pinfunction "HI_2") (pintype "passive"))
    )
    (net (code "2") (name "/AUX_L") (class "Default")
      (node (ref "R21") (pin "1") (pinfunction "1_1") (pintype "passive"))
      (node (ref "U2") (pin "29") (pinfunction "PB10_29") (pintype "passive"))
      (node (ref "U5") (pin "3") (pinfunction "LI_3") (pintype "passive"))
    )
    (net (code "3") (name "/AUX_TEMP") (class "Default")
      (node (ref "C18") (pin "2") (pinfunction "2_2") (pintype "passive"))
      (node (ref "R8") (pin "1") (pinfunction "1_1") (pintype "passive"))
      (node (ref "RT2") (pin "1") (pinfunction "1_1") (pintype "passive"))
      (node (ref "U2") (pin "21") (pinfunction "PA5_21") (pintype "passive"))
    )
    (net (code "4") (name "/BOOT0") (class "Default")
      (node (ref "R3") (pin "1") (pinfunction "1_1") (pintype "passive"))
      (node (ref "U2") (pin "60") (pinfunction "BOOT0_60") (pintype "passive"))
    )
    (net (code "5") (name "/CAN_D") (class "Default")
      (node (ref "U1") (pin "1") (pinfunction "D_1") (pintype "passive"))
      (node (ref "U2") (pin "62") (pinfunction "PB9_62") (pintype "passive"))
    )
    (net (code "6") (name "/CAN_H") (class "Default")
      (node (ref "CN1") (pin "1") (pinfunction "1_1") (pintype "passive"))
      (node (ref "R1") (pin "1") (pinfunction "1_1") (pintype "passive"))
      (node (ref "U1") (pin "7") (pinfunction "CANH_7") (pintype "passive"))
    )
    (net (code "7") (name "/CAN_L") (class "Default")
      (node (ref "CN1") (pin "2") (pinfunction "2_2") (pintype "passive"))
      (node (ref "R1") (pin "2") (pinfunction "2_2") (pintype "passive"))
      (node (ref "U1") (pin "6") (pinfunction "CANL_6") (pintype "passive"))
    )
    (net (code "8") (name "/CAN_R") (class "Default")
      (node (ref "U1") (pin "4") (pinfunction "R_4") (pintype "passive"))
      (node (ref "U2") (pin "61") (pinfunction "PB8_61") (pintype "passive"))
    )
    (net (code "9") (name "/ENC_A") (class "Default")
      (node (ref "CN5") (pin "4") (pinfunction "4_4") (pintype "passive"))
      (node (ref "R13") (pin "2") (pinfunction "2_2") (pintype "passive"))
      (node (ref "U2") (pin "56") (pinfunction "PB4(NJTRST)_56") (pintype "passive"))
    )
    (net (code "10") (name "/ENC_B") (class "Default")
      (node (ref "CN5") (pin "3") (pinfunction "3_3") (pintype "passive"))
      (node (ref "R12") (pin "2") (pinfunction "2_2") (pintype "passive"))
      (node (ref "U2") (pin "57") (pinfunction "PB5_57") (pintype "passive"))
    )
    (net (code "11") (name "/ENC_CS") (class "Default")
      (node (ref "U2") (pin "24") (pinfunction "PC4_24") (pintype "passive"))
      (node (ref "U8") (pin "1") (pinfunction "CSN_1") (pintype "passive"))
    )
    (net (code "12") (name "/ENC_Z") (class "Default")
      (node (ref "CN5") (pin "2") (pinfunction "2_2") (pintype "passive"))
      (node (ref "R7") (pin "2") (pinfunction "2_2") (pintype "passive"))
      (node (ref "U2") (pin "40") (pinfunction "PC9_40") (pintype "passive"))
    )
    (net (code "13") (name "/EN_GATE") (class "Default")
      (node (ref "U2") (pin "33") (pinfunction "PB12_33") (pintype "passive"))
      (node (ref "U4") (pin "12") (pinfunction "EN_GATE_12") (pintype "passive"))
    )
    (net (code "14") (name "/GPIO_1") (class "Default")
      (node (ref "CN3") (pin "2") (pinfunction "2_2") (pintype "passive"))
      (node (ref "U2") (pin "14") (pinfunction "PA0-WKUP(PA0)_14") (pintype "passive"))
      (node (ref "U3") (pin "9") (pinfunction "RXD_9") (pintype "passive"))
    )
    (net (code "15") (name "/GPIO_2") (class "Default")
      (node (ref "CN3") (pin "3") (pinfunction "3_3") (pintype "passive"))
      (node (ref "U2") (pin "15") (pinfunction "PA1_15") (pintype "passive"))
      (node (ref "U3") (pin "8") (pinfunction "TXD_8") (pintype "passive"))
    )
    (net (code "16") (name "/GPIO_4") (class "Default")
      (node (ref "CN4") (pin "3") (pinfunction "3_3") (pintype "passive"))
      (node (ref "U2") (pin "17") (pinfunction "PA3_17") (pintype "passive"))
    )
    (net (code "17") (name "/GPIO_8") (class "Default")
      (node (ref "CN4") (pin "2") (pinfunction "2_2") (pintype "passive"))
      (node (ref "U2") (pin "55") (pinfunction "PB3(JTDOTRACESWO)_55") (pintype "passive"))
    )
    (net (code "18") (name "/M0_AH") (class "Default")
      (node (ref "U2") (pin "41") (pinfunction "PA8_41") (pintype "passive"))
      (node (ref "U4") (pin "13") (pinfunction "INH_A_13") (pintype "passive"))
    )
    (net (code "19") (name "/M0_AL") (class "Default")
      (node (ref "U2") (pin "34") (pinfunction "PB13_34") (pintype "passive"))
      (node (ref "U4") (pin "14") (pinfunction "INL_A_14") (pintype "passive"))
    )
    (net (code "20") (name "/M0_BH") (class "Default")
      (node (ref "TP6") (pin "1") (pinfunction "1_1") (pintype "passive"))
      (node (ref "U2") (pin "42") (pinfunction "PA9_42") (pintype "passive"))
      (node (ref "U4") (pin "15") (pinfunction "INH_B_15") (pintype "passive"))
    )
    (net (code "21") (name "/M0_BL") (class "Default")
      (node (ref "U2") (pin "35") (pinfunction "PB14_35") (pintype "passive"))
      (node (ref "U4") (pin "16") (pinfunction "INL_B_16") (pintype "passive"))
    )
    (net (code "22") (name "/M0_CH") (class "Default")
      (node (ref "TP4") (pin "1") (pinfunction "1_1") (pintype "passive"))
      (node (ref "U2") (pin "43") (pinfunction "PA10_43") (pintype "passive"))
      (node (ref "U4") (pin "17") (pinfunction "INH_C_17") (pintype "passive"))
    )
    (net (code "23") (name "/M0_CL") (class "Default")
      (node (ref "U2") (pin "36") (pinfunction "PB15_36") (pintype "passive"))
      (node (ref "U4") (pin "18") (pinfunction "INL_C_18") (pintype "passive"))
    )
    (net (code "24") (name "/M0_GH_A") (class "Default")
      (node (ref "R16") (pin "2") (pinfunction "2_2") (pintype "passive"))
      (node (ref "U4") (pin "43") (pinfunction "GH_A_43") (pintype "passive"))
    )
    (net (code "25") (name "/M0_GH_B") (class "Default")
      (node (ref "R24") (pin "2") (pinfunction "2_2") (pintype "passive"))
      (node (ref "U4") (pin "38") (pinfunction "GH_B_38") (pintype "passive"))
    )
    (net (code "26") (name "/M0_GH_C") (class "Default")
      (node (ref "R30") (pin "2") (pinfunction "2_2") (pintype "passive"))
      (node (ref "U4") (pin "33") (pinfunction "GH_C_33") (pintype "passive"))
    )
    (net (code "27") (name "/M0_GL_A") (class "Default")
      (node (ref "R17") (pin "2") (pinfunction "2_2") (pintype "passive"))
      (node (ref "U4") (pin "41") (pinfunction "GL_C_41") (pintype "passive"))
    )
    (net (code "28") (name "/M0_GL_B") (class "Default")
      (node (ref "R23") (pin "2") (pinfunction "2_2") (pintype "passive"))
      (node (ref "U4") (pin "36") (pinfunction "GL_B_36") (pintype "passive"))
    )
    (net (code "29") (name "/M0_GL_C") (class "Default")
      (node (ref "R31") (pin "2") (pinfunction "2_2") (pintype "passive"))
      (node (ref "U4") (pin "31") (pinfunction "GL_C_31") (pintype "passive"))
    )
    (net (code "30") (name "/M0_S1_N") (class "Default")
      (node (ref "C30") (pin "2") (pinfunction "2_2") (pintype "passive"))
      (node (ref "R25") (pin "1") (pinfunction "1_1") (pintype "passive"))
      (node (ref "U4") (pin "29") (pinfunction "SN1_29") (pintype "passive"))
    )
    (net (code "31") (name "/M0_S1_P") (class "Default")
      (node (ref "C30") (pin "1") (pinfunction "1_1") (pintype "passive"))
      (node (ref "R26") (pin "1") (pinfunction "1_1") (pintype "passive"))
      (node (ref "U4") (pin "28") (pinfunction "SP1_28") (pintype "passive"))
    )
    (net (code "32") (name "/M0_S2_N") (class "Default")
      (node (ref "C38") (pin "2") (pinfunction "2_2") (pintype "passive"))
      (node (ref "R32") (pin "1") (pinfunction "1_1") (pintype "passive"))
      (node (ref "U4") (pin "27") (pinfunction "SN2_27") (pintype "passive"))
    )
    (net (code "33") (name "/M0_S2_P") (class "Default")
      (node (ref "C38") (pin "1") (pinfunction "1_1") (pintype "passive"))
      (node (ref "R33") (pin "1") (pinfunction "1_1") (pintype "passive"))
      (node (ref "U4") (pin "26") (pinfunction "SP2_26") (pintype "passive"))
    )
    (net (code "34") (name "/M0_SH_A") (class "Default")
      (node (ref "C35") (pin "1") (pinfunction "1_1") (pintype "passive"))
      (node (ref "Q1") (pin "D") (pinfunction "D_D") (pintype "passive"))
      (node (ref "Q2") (pin "S") (pinfunction "S_S") (pintype "passive"))
      (node (ref "U4") (pin "42") (pinfunction "SH_A_42") (pintype "passive"))
    )
    (net (code "35") (name "/M0_SH_B") (class "Default")
      (node (ref "C36") (pin "1") (pinfunction "1_1") (pintype "passive"))
      (node (ref "Q3") (pin "S") (pinfunction "S_S") (pintype "passive"))
      (node (ref "Q4") (pin "D") (pinfunction "D_D") (pintype "passive"))
      (node (ref "U4") (pin "37") (pinfunction "SH_B_37") (pintype "passive"))
    )
    (net (code "36") (name "/M0_SH_C") (class "Default")
      (node (ref "C37") (pin "1") (pinfunction "1_1") (pintype "passive"))
      (node (ref "Q7") (pin "S") (pinfunction "S_S") (pintype "passive"))
      (node (ref "Q8") (pin "D") (pinfunction "D_D") (pintype "passive"))
      (node (ref "U4") (pin "32") (pinfunction "SH_C_32") (pintype "passive"))
    )
    (net (code "37") (name "/M0_SL_B") (class "Default")
      (node (ref "Q4") (pin "S") (pinfunction "S_S") (pintype "passive"))
      (node (ref "R25") (pin "2") (pinfunction "2_2") (pintype "passive"))
      (node (ref "R27") (pin "2") (pinfunction "2_2") (pintype "passive"))
      (node (ref "U4") (pin "35") (pinfunction "SL_B_35") (pintype "passive"))
    )
    (net (code "38") (name "/M0_SL_C") (class "Default")
      (node (ref "Q8") (pin "S") (pinfunction "S_S") (pintype "passive"))
      (node (ref "R32") (pin "2") (pinfunction "2_2") (pintype "passive"))
      (node (ref "R34") (pin "2") (pinfunction "2_2") (pintype "passive"))
      (node (ref "U4") (pin "30") (pinfunction "SL_C_30") (pintype "passive"))
    )
    (net (code "39") (name "/M0_SO1") (class "Default")
      (node (ref "C24") (pin "2") (pinfunction "2_2") (pintype "passive"))
      (node (ref "R18") (pin "2") (pinfunction "2_2") (pintype "passive"))
      (node (ref "U2") (pin "8") (pinfunction "PC0_8") (pintype "passive"))
    )
    (net (code "40") (name "/M0_SO2") (class "Default")
      (node (ref "C27") (pin "2") (pinfunction "2_2") (pintype "passive"))
      (node (ref "R20") (pin "2") (pinfunction "2_2") (pintype "passive"))
      (node (ref "U2") (pin "9") (pinfunction "PC1_9") (pintype "passive"))
    )
    (net (code "41") (name "/M0_TEMP") (class "Default")
      (node (ref "C16") (pin "2") (pinfunction "2_2") (pintype "passive"))
      (node (ref "R5") (pin "1") (pinfunction "1_1") (pintype "passive"))
      (node (ref "RT1") (pin "1") (pinfunction "1_1") (pintype "passive"))
      (node (ref "U2") (pin "25") (pinfunction "PC5_25") (pintype "passive"))
    )
    (net (code "42") (name "/M_DRIVER_CS") (class "Default")
      (node (ref "U2") (pin "2") (pinfunction "PC13_2") (pintype "passive"))
      (node (ref "U4") (pin "4") (pinfunction "nSCS_4") (pintype "passive"))
    )
    (net (code "43") (name "/NRST") (class "Default")
      (node (ref "C20") (pin "2") (pinfunction "2_2") (pintype "passive"))
      (node (ref "R11") (pin "2") (pinfunction "2_2") (pintype "passive"))
      (node (ref "SW1") (pin "2") (pinfunction "2_2") (pintype "passive"))
      (node (ref "U2") (pin "7") (pinfunction "NRST_7") (pintype "passive"))
    )
    (net (code "44") (name "/RES") (class "Default")
      (node (ref "C32") (pin "1") (pinfunction "1_1") (pintype "passive"))
      (node (ref "Q5") (pin "S") (pinfunction "S_S") (pintype "passive"))
      (node (ref "Q6") (pin "D") (pinfunction "D_D") (pintype "passive"))
      (node (ref "U5") (pin "6") (pinfunction "HS_6") (pintype "passive"))
    )
    (net (code "45") (name "/SPI_MISO") (class "Default")
      (node (ref "U2") (pin "52") (pinfunction "PC11_52") (pintype "passive"))
      (node (ref "U4") (pin "6") (pinfunction "SDO_6") (pintype "passive"))
      (node (ref "U8") (pin "3") (pinfunction "MISO_3") (pintype "passive"))
    )
    (net (code "46") (name "/SPI_MOSI") (class "Default")
      (node (ref "U2") (pin "53") (pinfunction "PC12_53") (pintype "passive"))
      (node (ref "U4") (pin "5") (pinfunction "SDI_5") (pintype "passive"))
      (node (ref "U8") (pin "4") (pinfunction "MOSI_4") (pintype "passive"))
    )
    (net (code "47") (name "/SPI_SCK") (class "Default")
      (node (ref "U2") (pin "51") (pinfunction "PC10_51") (pintype "passive"))
      (node (ref "U4") (pin "7") (pinfunction "SCLK_7") (pintype "passive"))
      (node (ref "U8") (pin "2") (pinfunction "SCK_2") (pintype "passive"))
    )
    (net (code "48") (name "/SWCLK") (class "Default")
      (node (ref "CN2") (pin "2") (pinfunction "2_2") (pintype "passive"))
      (node (ref "U2") (pin "49") (pinfunction "PA14(JTCK-SWCLK)_49") (pintype "passive"))
    )
    (net (code "49") (name "/SWDIO") (class "Default")
      (node (ref "CN2") (pin "3") (pinfunction "3_3") (pintype "passive"))
      (node (ref "U2") (pin "46") (pinfunction "PA13(JTMS-SWDIO)_46") (pintype "passive"))
    )
    (net (code "50") (name "/USB_DM") (class "Default")
      (node (ref "R14") (pin "1") (pinfunction "1_1") (pintype "passive"))
      (node (ref "U2") (pin "44") (pinfunction "PA11_44") (pintype "passive"))
    )
    (net (code "51") (name "/USB_DP") (class "Default")
      (node (ref "R15") (pin "1") (pinfunction "1_1") (pintype "passive"))
      (node (ref "U2") (pin "45") (pinfunction "PA12_45") (pintype "passive"))
    )
    (net (code "52") (name "/VBUS_S") (class "Default")
      (node (ref "C17") (pin "2") (pinfunction "2_2") (pintype "passive"))
      (node (ref "R10") (pin "1") (pinfunction "1_1") (pintype "passive"))
      (node (ref "R9") (pin "2") (pinfunction "2_2") (pintype "passive"))
      (node (ref "U2") (pin "22") (pinfunction "PA6_22") (pintype "passive"))
    )
    (net (code "53") (name "/_USB_DM") (class "Default")
      (node (ref "R14") (pin "2") (pinfunction "2_2") (pintype "passive"))
      (node (ref "USBC1") (pin "A7") (pinfunction "DN1_A7") (pintype "passive"))
    )
    (net (code "54") (name "/_USB_DP") (class "Default")
      (node (ref "R15") (pin "2") (pinfunction "2_2") (pintype "passive"))
      (node (ref "USBC1") (pin "A6") (pinfunction "DP1_A6") (pintype "passive"))
    )
    (net (code "55") (name "/nFAULT") (class "Default")
      (node (ref "LED2") (pin "2") (pinfunction "K_2") (pintype "passive"))
      (node (ref "U2") (pin "54") (pinfunction "PD2_54") (pintype "passive"))
      (node (ref "U4") (pin "2") (pinfunction "nFAULT_2") (pintype "passive"))
    )
    (net (code "56") (name "5V") (class "Default")
      (node (ref "C42") (pin "2") (pinfunction "2_2") (pintype "passive"))
      (node (ref "C53") (pin "2") (pinfunction "2_2") (pintype "passive"))
      (node (ref "C61") (pin "2") (pinfunction "2_2") (pintype "passive"))
      (node (ref "CN2") (pin "1") (pinfunction "1_1") (pintype "passive"))
      (node (ref "CN3") (pin "1") (pinfunction "1_1") (pintype "passive"))
      (node (ref "CN4") (pin "1") (pinfunction "1_1") (pintype "passive"))
      (node (ref "D1") (pin "2") (pinfunction "K_2") (pintype "passive"))
      (node (ref "L1") (pin "2") (pinfunction "2_2") (pintype "passive"))
      (node (ref "R40") (pin "1") (pinfunction "1_1") (pintype "passive"))
      (node (ref "TP5") (pin "1") (pinfunction "1_1") (pintype "passive"))
      (node (ref "U6") (pin "1") (pinfunction "VIN_1") (pintype "passive"))
      (node (ref "U6") (pin "3") (pinfunction "CE_3") (pintype "passive"))
      (node (ref "U9") (pin "1") (pinfunction "IN_1") (pintype "passive"))
      (node (ref "U9") (pin "3") (pinfunction "EN_3") (pintype "passive"))
    )
    (net (code "57") (name "AGND") (class "Default")
      (node (ref "C1") (pin "1") (pinfunction "1_1") (pintype "passive"))
      (node (ref "C10") (pin "1") (pinfunction "1_1") (pintype "passive"))
      (node (ref "C11") (pin "1") (pinfunction "1_1") (pintype "passive"))
      (node (ref "C12") (pin "1") (pinfunction "1_1") (pintype "passive"))
      (node (ref "C13") (pin "1") (pinfunction "1_1") (pintype "passive"))
      (node (ref "C14") (pin "1") (pinfunction "1_1") (pintype "passive"))
      (node (ref "C15") (pin "1") (pinfunction "1_1") (pintype "passive"))
      (node (ref "C16") (pin "1") (pinfunction "1_1") (pintype "passive"))
      (node (ref "C17") (pin "1") (pinfunction "1_1") (pintype "passive"))
      (node (ref "C18") (pin "1") (pinfunction "1_1") (pintype "passive"))
      (node (ref "C19") (pin "1") (pinfunction "1_1") (pintype "passive"))
      (node (ref "C2") (pin "1") (pinfunction "1_1") (pintype "passive"))
      (node (ref "C20") (pin "1") (pinfunction "1_1") (pintype "passive"))
      (node (ref "C21") (pin "2") (pinfunction "2_2") (pintype "passive"))
      (node (ref "C22") (pin "2") (pinfunction "2_2") (pintype "passive"))
      (node (ref "C23") (pin "1") (pinfunction "1_1") (pintype "passive"))
      (node (ref "C24") (pin "1") (pinfunction "1_1") (pintype "passive"))
      (node (ref "C27") (pin "1") (pinfunction "1_1") (pintype "passive"))
      (node (ref "C28") (pin "1") (pinfunction "1_1") (pintype "passive"))
      (node (ref "C29") (pin "1") (pinfunction "1_1") (pintype "passive"))
      (node (ref "C3") (pin "1") (pinfunction "1_1") (pintype "passive"))
      (node (ref "C39") (pin "1") (pinfunction "1_1") (pintype "passive"))
      (node (ref "C4") (pin "1") (pinfunction "1_1") (pintype "passive"))
      (node (ref "C41") (pin "1") (pinfunction "1_1") (pintype "passive"))
      (node (ref "C42") (pin "1") (pinfunction "1_1") (pintype "passive"))
      (node (ref "C47") (pin "1") (pinfunction "1_1") (pintype "passive"))
      (node (ref "C49") (pin "1") (pinfunction "1_1") (pintype "passive"))
      (node (ref "C5") (pin "1") (pinfunction "1_1") (pintype "passive"))
      (node (ref "C51") (pin "1") (pinfunction "1_1") (pintype "passive"))
      (node (ref "C53") (pin "1") (pinfunction "1_1") (pintype "passive"))
      (node (ref "C58") (pin "1") (pinfunction "1_1") (pintype "passive"))
      (node (ref "C59") (pin "1") (pinfunction "1_1") (pintype "passive"))
      (node (ref "C6") (pin "1") (pinfunction "1_1") (pintype "passive"))
      (node (ref "C61") (pin "1") (pinfunction "1_1") (pintype "passive"))
      (node (ref "C62") (pin "1") (pinfunction "1_1") (pintype "passive"))
      (node (ref "C7") (pin "1") (pinfunction "1_1") (pintype "passive"))
      (node (ref "C8") (pin "1") (pinfunction "1_1") (pintype "passive"))
      (node (ref "C9") (pin "1") (pinfunction "1_1") (pintype "passive"))
      (node (ref "CN1") (pin "3") (pinfunction "3_3") (pintype "passive"))
      (node (ref "CN1") (pin "4") (pinfunction "4_4") (pintype "passive"))
      (node (ref "CN2") (pin "4") (pinfunction "4_4") (pintype "passive"))
      (node (ref "CN2") (pin "5") (pinfunction "5_5") (pintype "passive"))
      (node (ref "CN2") (pin "6") (pinfunction "6_6") (pintype "passive"))
      (node (ref "CN3") (pin "4") (pinfunction "4_4") (pintype "passive"))
      (node (ref "CN3") (pin "5") (pinfunction "5_5") (pintype "passive"))
      (node (ref "CN3") (pin "6") (pinfunction "6_6") (pintype "passive"))
      (node (ref "CN4") (pin "4") (pinfunction "4_4") (pintype "passive"))
      (node (ref "CN4") (pin "5") (pinfunction "5_5") (pintype "passive"))
      (node (ref "CN4") (pin "6") (pinfunction "6_6") (pintype "passive"))
      (node (ref "CN5") (pin "5") (pinfunction "5_5") (pintype "passive"))
      (node (ref "CN5") (pin "6") (pinfunction "6_6") (pintype "passive"))
      (node (ref "CN5") (pin "7") (pinfunction "7_7") (pintype "passive"))
      (node (ref "D4") (pin "1") (pinfunction "A_1") (pintype "passive"))
      (node (ref "D5") (pin "1") (pinfunction "A_1") (pintype "passive"))
      (node (ref "LED1") (pin "2") (pinfunction "K_2") (pintype "passive"))
      (node (ref "R10") (pin "2") (pinfunction "2_2") (pintype "passive"))
      (node (ref "R19") (pin "2") (pinfunction "2_2") (pintype "passive"))
      (node (ref "R21") (pin "2") (pinfunction "2_2") (pintype "passive"))
      (node (ref "R22") (pin "2") (pinfunction "2_2") (pintype "passive"))
      (node (ref "R3") (pin "2") (pinfunction "2_2") (pintype "passive"))
      (node (ref "R36") (pin "2") (pinfunction "2_2") (pintype "passive"))
      (node (ref "R38") (pin "2") (pinfunction "2_2") (pintype "passive"))
      (node (ref "R39") (pin "2") (pinfunction "2_2") (pintype "passive"))
      (node (ref "R5") (pin "2") (pinfunction "2_2") (pintype "passive"))
      (node (ref "R8") (pin "2") (pinfunction "2_2") (pintype "passive"))
      (node (ref "SW1") (pin "1") (pinfunction "1_1") (pintype "passive"))
      (node (ref "U1") (pin "2") (pinfunction "GND_2") (pintype "passive"))
      (node (ref "U1") (pin "8") (pinfunction "RS_8") (pintype "passive"))
      (node (ref "U1") (pin "9") (pinfunction "EP_9") (pintype "passive"))
      (node (ref "U2") (pin "12") (pinfunction "VSSA_12") (pintype "passive"))
      (node (ref "U2") (pin "18") (pinfunction "VSS_18") (pintype "passive"))
      (node (ref "U2") (pin "63") (pinfunction "VSS_63") (pintype "passive"))
      (node (ref "U3") (pin "3") (pinfunction "GND_3") (pintype "passive"))
      (node (ref "U4") (pin "24") (pinfunction "AGND_24") (pintype "passive"))
      (node (ref "U4") (pin "46") (pinfunction "GND_46") (pintype "passive"))
      (node (ref "U4") (pin "47") (pinfunction "GND_47") (pintype "passive"))
      (node (ref "U4") (pin "48") (pinfunction "GND_48") (pintype "passive"))
      (node (ref "U4") (pin "49") (pinfunction "EP_49") (pintype "passive"))
      (node (ref "U5") (pin "4") (pinfunction "VSS_4") (pintype "passive"))
      (node (ref "U6") (pin "2") (pinfunction "VSS_2") (pintype "passive"))
      (node (ref "U7") (pin "11") (pinfunction "TP_11") (pintype "passive"))
      (node (ref "U7") (pin "9") (pinfunction "GND_9") (pintype "passive"))
      (node (ref "U8") (pin "13") (pinfunction "GND_13") (pintype "passive"))
      (node (ref "U8") (pin "5") (pinfunction "TEST_5") (pintype "passive"))
      (node (ref "U9") (pin "2") (pinfunction "GND_2") (pintype "passive"))
      (node (ref "USBC1") (pin "0") (pinfunction "0_0") (pintype "passive"))
      (node (ref "USBC1") (pin "A1") (pinfunction "GND_A1") (pintype "passive"))
      (node (ref "USBC1") (pin "A12") (pinfunction "GND_A12") (pintype "passive"))
      (node (ref "USBC1") (pin "B1") (pinfunction "GND_B1") (pintype "passive"))
      (node (ref "USBC1") (pin "B12") (pinfunction "GND_B12") (pintype "passive"))
      (node (ref "X1") (pin "2") (pinfunction "GND_2") (pintype "passive"))
    )
    (net (code "58") (name "AVCC") (class "Default")
      (node (ref "C12") (pin "2") (pinfunction "2_2") (pintype "passive"))
      (node (ref "C15") (pin "2") (pinfunction "2_2") (pintype "passive"))
      (node (ref "C21") (pin "1") (pinfunction "1_1") (pintype "passive"))
      (node (ref "C62") (pin "2") (pinfunction "2_2") (pintype "passive"))
      (node (ref "TP3") (pin "1") (pinfunction "1_1") (pintype "passive"))
      (node (ref "U2") (pin "13") (pinfunction "VDDA_13") (pintype "passive"))
      (node (ref "U4") (pin "20") (pinfunction "REF_20") (pintype "passive"))
      (node (ref "U9") (pin "5") (pinfunction "OUT_5") (pintype "passive"))
    )
    (net (code "59") (name "DCBUS") (class "Default")
      (node (ref "C26") (pin "2") (pinfunction "2_2") (pintype "passive"))
      (node (ref "C31") (pin "2") (pinfunction "2_2") (pintype "passive"))
      (node (ref "C33") (pin "2") (pinfunction "2_2") (pintype "passive"))
      (node (ref "C34") (pin "2") (pinfunction "2_2") (pintype "passive"))
      (node (ref "C40") (pin "2") (pinfunction "2_2") (pintype "passive"))
      (node (ref "C44") (pin "2") (pinfunction "2_2") (pintype "passive"))
      (node (ref "C46") (pin "2") (pinfunction "2_2") (pintype "passive"))
      (node (ref "C48") (pin "2") (pinfunction "2_2") (pintype "passive"))
      (node (ref "C50") (pin "2") (pinfunction "2_2") (pintype "passive"))
      (node (ref "C52") (pin "2") (pinfunction "2_2") (pintype "passive"))
      (node (ref "C54") (pin "2") (pinfunction "2_2") (pintype "passive"))
      (node (ref "C55") (pin "2") (pinfunction "2_2") (pintype "passive"))
      (node (ref "C57") (pin "2") (pinfunction "2_2") (pintype "passive"))
      (node (ref "C60") (pin "2") (pinfunction "2_2") (pintype "passive"))
      (node (ref "C63") (pin "2") (pinfunction "2_2") (pintype "passive"))
      (node (ref "D3") (pin "1") (pinfunction "A_1") (pintype "passive"))
      (node (ref "Q2") (pin "D") (pinfunction "D_D") (pintype "passive"))
      (node (ref "Q3") (pin "D") (pinfunction "D_D") (pintype "passive"))
      (node (ref "Q5") (pin "D") (pinfunction "D_D") (pintype "passive"))
      (node (ref "Q7") (pin "D") (pinfunction "D_D") (pintype "passive"))
      (node (ref "R35") (pin "1") (pinfunction "1_1") (pintype "passive"))
      (node (ref "R9") (pin "1") (pinfunction "1_1") (pintype "passive"))
      (node (ref "U4") (pin "25") (pinfunction "PVDD_25") (pintype "passive"))
      (node (ref "U7") (pin "2") (pinfunction "VIN_2") (pintype "passive"))
    )
    (net (code "60") (name "GVDD") (class "Default")
      (node (ref "C23") (pin "2") (pinfunction "2_2") (pintype "passive"))
      (node (ref "C29") (pin "2") (pinfunction "2_2") (pintype "passive"))
      (node (ref "D2") (pin "1") (pinfunction "A_1") (pintype "passive"))
      (node (ref "TP2") (pin "1") (pinfunction "1_1") (pintype "passive"))
      (node (ref "U4") (pin "9") (pinfunction "GVDD_9") (pintype "passive"))
      (node (ref "U5") (pin "1") (pinfunction "VDD_1") (pintype "passive"))
    )
    (net (code "61") (name "Net-(C43-Pad2)") (class "Default")
      (node (ref "C43") (pin "2") (pinfunction "2_2") (pintype "passive"))
      (node (ref "R35") (pin "2") (pinfunction "2_2") (pintype "passive"))
    )
    (net (code "62") (name "Net-(C49-Pad2)") (class "Default")
      (node (ref "C49") (pin "2") (pinfunction "2_2") (pintype "passive"))
      (node (ref "R37") (pin "2") (pinfunction "2_2") (pintype "passive"))
    )
    (net (code "63") (name "Net-(D1-A)") (class "Default")
      (node (ref "D1") (pin "1") (pinfunction "A_1") (pintype "passive"))
      (node (ref "F1") (pin "2") (pintype "passive"))
    )
    (net (code "64") (name "Net-(D2-K)") (class "Default")
      (node (ref "C32") (pin "2") (pinfunction "2_2") (pintype "passive"))
      (node (ref "D2") (pin "2") (pinfunction "K_2") (pintype "passive"))
      (node (ref "U5") (pin "8") (pinfunction "HB_8") (pintype "passive"))
    )
    (net (code "65") (name "Net-(D4-K)") (class "Default")
      (node (ref "C56") (pin "2") (pinfunction "2_2") (pintype "passive"))
      (node (ref "D4") (pin "2") (pinfunction "K_2") (pintype "passive"))
      (node (ref "L1") (pin "1") (pinfunction "1_1") (pintype "passive"))
      (node (ref "U7") (pin "10") (pinfunction "PH_10") (pintype "passive"))
    )
    (net (code "66") (name "Net-(LED1-A)") (class "Default")
      (node (ref "LED1") (pin "1") (pinfunction "A_1") (pintype "passive"))
      (node (ref "R4") (pin "1") (pinfunction "1_1") (pintype "passive"))
    )
    (net (code "67") (name "Net-(LED2-A)") (class "Default")
      (node (ref "LED2") (pin "1") (pinfunction "A_1") (pintype "passive"))
      (node (ref "R6") (pin "1") (pinfunction "1_1") (pintype "passive"))
    )
    (net (code "68") (name "Net-(Q1-PadG)") (class "Default")
      (node (ref "Q1") (pin "G") (pinfunction "G_G") (pintype "passive"))
      (node (ref "R17") (pin "1") (pinfunction "1_1") (pintype "passive"))
    )
    (net (code "69") (name "Net-(Q2-PadG)") (class "Default")
      (node (ref "Q2") (pin "G") (pinfunction "G_G") (pintype "passive"))
      (node (ref "R16") (pin "1") (pinfunction "1_1") (pintype "passive"))
    )
    (net (code "70") (name "Net-(Q3-PadG)") (class "Default")
      (node (ref "Q3") (pin "G") (pinfunction "G_G") (pintype "passive"))
      (node (ref "R24") (pin "1") (pinfunction "1_1") (pintype "passive"))
    )
    (net (code "71") (name "Net-(Q4-PadG)") (class "Default")
      (node (ref "Q4") (pin "G") (pinfunction "G_G") (pintype "passive"))
      (node (ref "R23") (pin "1") (pinfunction "1_1") (pintype "passive"))
    )
    (net (code "72") (name "Net-(Q5-PadG)") (class "Default")
      (node (ref "Q5") (pin "G") (pinfunction "G_G") (pintype "passive"))
      (node (ref "R28") (pin "1") (pinfunction "1_1") (pintype "passive"))
    )
    (net (code "73") (name "Net-(Q6-PadG)") (class "Default")
      (node (ref "Q6") (pin "G") (pinfunction "G_G") (pintype "passive"))
      (node (ref "R29") (pin "1") (pinfunction "1_1") (pintype "passive"))
    )
    (net (code "74") (name "Net-(Q7-PadG)") (class "Default")
      (node (ref "Q7") (pin "G") (pinfunction "G_G") (pintype "passive"))
      (node (ref "R30") (pin "1") (pinfunction "1_1") (pintype "passive"))
    )
    (net (code "75") (name "Net-(Q8-PadG)") (class "Default")
      (node (ref "Q8") (pin "G") (pinfunction "G_G") (pintype "passive"))
      (node (ref "R31") (pin "1") (pinfunction "1_1") (pintype "passive"))
    )
    (net (code "76") (name "Net-(U2A-PH0-OSC_IN(PH0))") (class "Default")
      (node (ref "R2") (pin "1") (pinfunction "1_1") (pintype "passive"))
      (node (ref "U2") (pin "5") (pinfunction "PH0-OSC_IN(PH0)_5") (pintype "passive"))
    )
    (net (code "77") (name "Net-(U2A-VCAP_1)") (class "Default")
      (node (ref "C14") (pin "2") (pinfunction "2_2") (pintype "passive"))
      (node (ref "U2") (pin "31") (pinfunction "VCAP_1_31") (pintype "passive"))
    )
    (net (code "78") (name "Net-(U2A-VCAP_2)") (class "Default")
      (node (ref "C11") (pin "2") (pinfunction "2_2") (pintype "passive"))
      (node (ref "U2") (pin "47") (pinfunction "VCAP_2_47") (pintype "passive"))
    )
    (net (code "79") (name "Net-(U3-UD+)") (class "Default")
      (node (ref "U3") (pin "1") (pinfunction "UD+_1") (pintype "passive"))
      (node (ref "USBC1") (pin "B6") (pinfunction "DP2_B6") (pintype "passive"))
    )
    (net (code "80") (name "Net-(U3-UD-)") (class "Default")
      (node (ref "U3") (pin "2") (pinfunction "UD-_2") (pintype "passive"))
      (node (ref "USBC1") (pin "B7") (pinfunction "DN2_B7") (pintype "passive"))
    )
    (net (code "81") (name "Net-(U4-AVDD)") (class "Default")
      (node (ref "C28") (pin "2") (pinfunction "2_2") (pintype "passive"))
      (node (ref "U4") (pin "23") (pinfunction "AVDD_23") (pintype "passive"))
    )
    (net (code "82") (name "Net-(U4-BST_A)") (class "Default")
      (node (ref "C35") (pin "2") (pinfunction "2_2") (pintype "passive"))
      (node (ref "U4") (pin "44") (pinfunction "BST_A_44") (pintype "passive"))
    )
    (net (code "83") (name "Net-(U4-BST_B)") (class "Default")
      (node (ref "C36") (pin "2") (pinfunction "2_2") (pintype "passive"))
      (node (ref "U4") (pin "39") (pinfunction "BST_B_39") (pintype "passive"))
    )
    (net (code "84") (name "Net-(U4-BST_C)") (class "Default")
      (node (ref "C37") (pin "2") (pinfunction "2_2") (pintype "passive"))
      (node (ref "U4") (pin "34") (pinfunction "BST_C_34") (pintype "passive"))
    )
    (net (code "85") (name "Net-(U4-CP1)") (class "Default")
      (node (ref "C25") (pin "1") (pinfunction "1_1") (pintype "passive"))
      (node (ref "U4") (pin "10") (pinfunction "CP1_10") (pintype "passive"))
    )
    (net (code "86") (name "Net-(U4-CP2)") (class "Default")
      (node (ref "C25") (pin "2") (pinfunction "2_2") (pintype "passive"))
      (node (ref "U4") (pin "11") (pinfunction "CP2_11") (pintype "passive"))
    )
    (net (code "87") (name "Net-(U4-DTC)") (class "Default")
      (node (ref "R19") (pin "1") (pinfunction "1_1") (pintype "passive"))
      (node (ref "U4") (pin "3") (pinfunction "DTC_3") (pintype "passive"))
    )
    (net (code "88") (name "Net-(U4-DVDD)") (class "Default")
      (node (ref "C22") (pin "1") (pinfunction "1_1") (pintype "passive"))
      (node (ref "U4") (pin "19") (pinfunction "DVDD_19") (pintype "passive"))
    )
    (net (code "89") (name "Net-(U4-SO1)") (class "Default")
      (node (ref "R18") (pin "1") (pinfunction "1_1") (pintype "passive"))
      (node (ref "U4") (pin "21") (pinfunction "SO1_21") (pintype "passive"))
    )
    (net (code "90") (name "Net-(U4-SO2)") (class "Default")
      (node (ref "R20") (pin "1") (pinfunction "1_1") (pintype "passive"))
      (node (ref "U4") (pin "22") (pinfunction "SO2_22") (pintype "passive"))
    )
    (net (code "91") (name "Net-(U5-HO)") (class "Default")
      (node (ref "R28") (pin "2") (pinfunction "2_2") (pintype "passive"))
      (node (ref "U5") (pin "7") (pinfunction "HO_7") (pintype "passive"))
    )
    (net (code "92") (name "Net-(U5-LO)") (class "Default")
      (node (ref "R29") (pin "2") (pinfunction "2_2") (pintype "passive"))
      (node (ref "U5") (pin "5") (pinfunction "LO_5") (pintype "passive"))
    )
    (net (code "93") (name "Net-(U7-BOOT)") (class "Default")
      (node (ref "C56") (pin "1") (pinfunction "1_1") (pintype "passive"))
      (node (ref "U7") (pin "1") (pinfunction "BOOT_1") (pintype "passive"))
    )
    (net (code "94") (name "Net-(U7-COMP)") (class "Default")
      (node (ref "C47") (pin "2") (pinfunction "2_2") (pintype "passive"))
      (node (ref "R37") (pin "1") (pinfunction "1_1") (pintype "passive"))
      (node (ref "U7") (pin "8") (pinfunction "COMP_8") (pintype "passive"))
    )
    (net (code "95") (name "Net-(U7-RT{slash}CLK)") (class "Default")
      (node (ref "R36") (pin "1") (pinfunction "1_1") (pintype "passive"))
      (node (ref "U7") (pin "5") (pinfunction "RT/CLK_5") (pintype "passive"))
    )
    (net (code "96") (name "Net-(U7-SS{slash}TR)") (class "Default")
      (node (ref "C45") (pin "2") (pinfunction "2_2") (pintype "passive"))
      (node (ref "U7") (pin "4") (pinfunction "SS/TR_4") (pintype "passive"))
    )
    (net (code "97") (name "Net-(U7-VSENSE)") (class "Default")
      (node (ref "R39") (pin "1") (pinfunction "1_1") (pintype "passive"))
      (node (ref "R40") (pin "2") (pinfunction "2_2") (pintype "passive"))
      (node (ref "U7") (pin "7") (pinfunction "VSENSE_7") (pintype "passive"))
    )
    (net (code "98") (name "Net-(X1-OUT)") (class "Default")
      (node (ref "R2") (pin "2") (pinfunction "2_2") (pintype "passive"))
      (node (ref "X1") (pin "3") (pinfunction "OUT_3") (pintype "passive"))
    )
    (net (code "99") (name "PGND") (class "Default")
      (node (ref "C26") (pin "1") (pinfunction "1_1") (pintype "passive"))
      (node (ref "C31") (pin "1") (pinfunction "1_1") (pintype "passive"))
      (node (ref "C33") (pin "1") (pinfunction "1_1") (pintype "passive"))
      (node (ref "C34") (pin "1") (pinfunction "1_1") (pintype "passive"))
      (node (ref "C40") (pin "1") (pinfunction "1_1") (pintype "passive"))
      (node (ref "C43") (pin "1") (pinfunction "1_1") (pintype "passive"))
      (node (ref "C44") (pin "1") (pinfunction "1_1") (pintype "passive"))
      (node (ref "C45") (pin "1") (pinfunction "1_1") (pintype "passive"))
      (node (ref "C46") (pin "1") (pinfunction "1_1") (pintype "passive"))
      (node (ref "C48") (pin "1") (pinfunction "1_1") (pintype "passive"))
      (node (ref "C50") (pin "1") (pinfunction "1_1") (pintype "passive"))
      (node (ref "C52") (pin "1") (pinfunction "1_1") (pintype "passive"))
      (node (ref "C54") (pin "1") (pinfunction "1_1") (pintype "passive"))
      (node (ref "C55") (pin "1") (pinfunction "1_1") (pintype "passive"))
      (node (ref "C57") (pin "1") (pinfunction "1_1") (pintype "passive"))
      (node (ref "C60") (pin "1") (pinfunction "1_1") (pintype "passive"))
      (node (ref "C63") (pin "1") (pinfunction "1_1") (pintype "passive"))
      (node (ref "D3") (pin "2") (pinfunction "K_2") (pintype "passive"))
      (node (ref "Q1") (pin "S") (pinfunction "S_S") (pintype "passive"))
      (node (ref "Q6") (pin "S") (pinfunction "S_S") (pintype "passive"))
      (node (ref "R26") (pin "2") (pinfunction "2_2") (pintype "passive"))
      (node (ref "R27") (pin "1") (pinfunction "1_1") (pintype "passive"))
      (node (ref "R33") (pin "2") (pinfunction "2_2") (pintype "passive"))
      (node (ref "R34") (pin "1") (pinfunction "1_1") (pintype "passive"))
      (node (ref "R38") (pin "1") (pinfunction "1_1") (pintype "passive"))
      (node (ref "U4") (pin "40") (pinfunction "SL_A_40") (pintype "passive"))
      (node (ref "U5") (pin "9") (pinfunction "EP_9") (pintype "passive"))
    )
    (net (code "100") (name "VCC") (class "Default")
      (node (ref "C1") (pin "2") (pinfunction "2_2") (pintype "passive"))
      (node (ref "C10") (pin "2") (pinfunction "2_2") (pintype "passive"))
      (node (ref "C13") (pin "2") (pinfunction "2_2") (pintype "passive"))
      (node (ref "C19") (pin "2") (pinfunction "2_2") (pintype "passive"))
      (node (ref "C2") (pin "2") (pinfunction "2_2") (pintype "passive"))
      (node (ref "C3") (pin "2") (pinfunction "2_2") (pintype "passive"))
      (node (ref "C39") (pin "2") (pinfunction "2_2") (pintype "passive"))
      (node (ref "C4") (pin "2") (pinfunction "2_2") (pintype "passive"))
      (node (ref "C41") (pin "2") (pinfunction "2_2") (pintype "passive"))
      (node (ref "C5") (pin "2") (pinfunction "2_2") (pintype "passive"))
      (node (ref "C51") (pin "2") (pinfunction "2_2") (pintype "passive"))
      (node (ref "C58") (pin "2") (pinfunction "2_2") (pintype "passive"))
      (node (ref "C59") (pin "2") (pinfunction "2_2") (pintype "passive"))
      (node (ref "C6") (pin "2") (pinfunction "2_2") (pintype "passive"))
      (node (ref "C7") (pin "2") (pinfunction "2_2") (pintype "passive"))
      (node (ref "C8") (pin "2") (pinfunction "2_2") (pintype "passive"))
      (node (ref "C9") (pin "2") (pinfunction "2_2") (pintype "passive"))
      (node (ref "CN5") (pin "1") (pinfunction "1_1") (pintype "passive"))
      (node (ref "D5") (pin "2") (pinfunction "K_2") (pintype "passive"))
      (node (ref "R11") (pin "1") (pinfunction "1_1") (pintype "passive"))
      (node (ref "R12") (pin "1") (pinfunction "1_1") (pintype "passive"))
      (node (ref "R13") (pin "1") (pinfunction "1_1") (pintype "passive"))
      (node (ref "R4") (pin "2") (pinfunction "2_2") (pintype "passive"))
      (node (ref "R6") (pin "2") (pinfunction "2_2") (pintype "passive"))
      (node (ref "R7") (pin "1") (pinfunction "1_1") (pintype "passive"))
      (node (ref "RT1") (pin "2") (pinfunction "2_2") (pintype "passive"))
      (node (ref "RT2") (pin "2") (pinfunction "2_2") (pintype "passive"))
      (node (ref "TP1") (pin "1") (pinfunction "1_1") (pintype "passive"))
      (node (ref "U1") (pin "3") (pinfunction "VCC_3") (pintype "passive"))
      (node (ref "U2") (pin "1") (pinfunction "VBAT_1") (pintype "passive"))
      (node (ref "U2") (pin "19") (pinfunction "VDD_19") (pintype "passive"))
      (node (ref "U2") (pin "32") (pinfunction "VDD_32") (pintype "passive"))
      (node (ref "U2") (pin "48") (pinfunction "VDD_48") (pintype "passive"))
      (node (ref "U2") (pin "64") (pinfunction "VDD_64") (pintype "passive"))
      (node (ref "U3") (pin "10") (pinfunction "V3_10") (pintype "passive"))
      (node (ref "U3") (pin "7") (pinfunction "VCC_7") (pintype "passive"))
      (node (ref "U4") (pin "45") (pinfunction "VDD_SPI_45") (pintype "passive"))
      (node (ref "U6") (pin "5") (pinfunction "VOUT_5") (pintype "passive"))
      (node (ref "U8") (pin "11") (pinfunction "VDD_11") (pintype "passive"))
      (node (ref "U8") (pin "12") (pinfunction "VDD3V3_12") (pintype "passive"))
      (node (ref "X1") (pin "4") (pinfunction "VCC_4") (pintype "passive"))
    )
    (net (code "101") (name "VUSB") (class "Default")
      (node (ref "F1") (pin "1") (pinfunction "1_1") (pintype "passive"))
      (node (ref "USBC1") (pin "A4") (pinfunction "VBUS_A4") (pintype "passive"))
      (node (ref "USBC1") (pin "A9") (pinfunction "VBUS_A9") (pintype "passive"))
      (node (ref "USBC1") (pin "B4") (pinfunction "VBUS_B4") (pintype "passive"))
      (node (ref "USBC1") (pin "B9") (pinfunction "VBUS_B9") (pintype "passive"))
    )
    (net (code "102") (name "unconnected-(U1-SHDN-Pad5)") (class "Default")
      (node (ref "U1") (pin "5") (pinfunction "SHDN_5") (pintype "passive+no_connect"))
    )
    (net (code "103") (name "unconnected-(U2A-PA2-Pad16)") (class "Default")
      (node (ref "U2") (pin "16") (pinfunction "PA2_16") (pintype "passive+no_connect"))
    )
    (net (code "104") (name "unconnected-(U2A-PA4-Pad20)") (class "Default")
      (node (ref "U2") (pin "20") (pinfunction "PA4_20") (pintype "passive+no_connect"))
    )
    (net (code "105") (name "unconnected-(U2A-PA7-Pad23)") (class "Default")
      (node (ref "U2") (pin "23") (pinfunction "PA7_23") (pintype "passive+no_connect"))
    )
    (net (code "106") (name "unconnected-(U2A-PA15(JTDI)-Pad50)") (class "Default")
      (node (ref "U2") (pin "50") (pinfunction "PA15(JTDI)_50") (pintype "passive+no_connect"))
    )
    (net (code "107") (name "unconnected-(U2A-PB0-Pad26)") (class "Default")
      (node (ref "U2") (pin "26") (pinfunction "PB0_26") (pintype "passive+no_connect"))
    )
    (net (code "108") (name "unconnected-(U2A-PB1-Pad27)") (class "Default")
      (node (ref "U2") (pin "27") (pinfunction "PB1_27") (pintype "passive+no_connect"))
    )
    (net (code "109") (name "unconnected-(U2A-PB2-BOOT1(PB2)-Pad28)") (class "Default")
      (node (ref "U2") (pin "28") (pinfunction "PB2-BOOT1(PB2)_28") (pintype "passive+no_connect"))
    )
    (net (code "110") (name "unconnected-(U2A-PB6-Pad58)") (class "Default")
      (node (ref "U2") (pin "58") (pinfunction "PB6_58") (pintype "passive+no_connect"))
    )
    (net (code "111") (name "unconnected-(U2A-PB7-Pad59)") (class "Default")
      (node (ref "U2") (pin "59") (pinfunction "PB7_59") (pintype "passive+no_connect"))
    )
    (net (code "112") (name "unconnected-(U2A-PC2-Pad10)") (class "Default")
      (node (ref "U2") (pin "10") (pinfunction "PC2_10") (pintype "passive+no_connect"))
    )
    (net (code "113") (name "unconnected-(U2A-PC3-Pad11)") (class "Default")
      (node (ref "U2") (pin "11") (pinfunction "PC3_11") (pintype "passive+no_connect"))
    )
    (net (code "114") (name "unconnected-(U2A-PC6-Pad37)") (class "Default")
      (node (ref "U2") (pin "37") (pinfunction "PC6_37") (pintype "passive+no_connect"))
    )
    (net (code "115") (name "unconnected-(U2A-PC7-Pad38)") (class "Default")
      (node (ref "U2") (pin "38") (pinfunction "PC7_38") (pintype "passive+no_connect"))
    )
    (net (code "116") (name "unconnected-(U2A-PC8-Pad39)") (class "Default")
      (node (ref "U2") (pin "39") (pinfunction "PC8_39") (pintype "passive+no_connect"))
    )
    (net (code "117") (name "unconnected-(U2A-PC14-OSC32_IN(PC14)-Pad3)") (class "Default")
      (node (ref "U2") (pin "3") (pinfunction "PC14-OSC32_IN(PC14)_3") (pintype "passive+no_connect"))
    )
    (net (code "118") (name "unconnected-(U2A-PC15-OSC32_OUT(PC15)-Pad4)") (class "Default")
      (node (ref "U2") (pin "4") (pinfunction "PC15-OSC32_OUT(PC15)_4") (pintype "passive+no_connect"))
    )
    (net (code "119") (name "unconnected-(U2A-PH1-OSC_OUT(PH1)-Pad6)") (class "Default")
      (node (ref "U2") (pin "6") (pinfunction "PH1-OSC_OUT(PH1)_6") (pintype "passive+no_connect"))
    )
    (net (code "120") (name "unconnected-(U3-CTS#-Pad5)") (class "Default")
      (node (ref "U3") (pin "5") (pinfunction "CTS#_5") (pintype "passive+no_connect"))
    )
    (net (code "121") (name "unconnected-(U3-RTS#-Pad4)") (class "Default")
      (node (ref "U3") (pin "4") (pinfunction "RTS#_4") (pintype "passive+no_connect"))
    )
    (net (code "122") (name "unconnected-(U3-TNOW-Pad6)") (class "Default")
      (node (ref "U3") (pin "6") (pinfunction "TNOW_6") (pintype "passive+no_connect"))
    )
    (net (code "123") (name "unconnected-(U4-DC_CAL-Pad8)") (class "Default")
      (node (ref "U4") (pin "8") (pinfunction "DC_CAL_8") (pintype "passive+no_connect"))
    )
    (net (code "124") (name "unconnected-(U4-nOCTW-Pad1)") (class "Default")
      (node (ref "U4") (pin "1") (pinfunction "nOCTW_1") (pintype "passive+no_connect"))
    )
    (net (code "125") (name "unconnected-(U6-NC-Pad4)") (class "Default")
      (node (ref "U6") (pin "4") (pinfunction "NC_4") (pintype "passive+no_connect"))
    )
    (net (code "126") (name "unconnected-(U7-EN-Pad3)") (class "Default")
      (node (ref "U7") (pin "3") (pinfunction "EN_3") (pintype "passive+no_connect"))
    )
    (net (code "127") (name "unconnected-(U7-PWRGD-Pad6)") (class "Default")
      (node (ref "U7") (pin "6") (pinfunction "PWRGD_6") (pintype "passive+no_connect"))
    )
    (net (code "128") (name "unconnected-(U8-A-Pad7)") (class "Default")
      (node (ref "U8") (pin "7") (pinfunction "A_7") (pintype "passive+no_connect"))
    )
    (net (code "129") (name "unconnected-(U8-B-Pad6)") (class "Default")
      (node (ref "U8") (pin "6") (pinfunction "B_6") (pintype "passive+no_connect"))
    )
    (net (code "130") (name "unconnected-(U8-I{slash}PWM-Pad14)") (class "Default")
      (node (ref "U8") (pin "14") (pinfunction "I/PWM_14") (pintype "passive+no_connect"))
    )
    (net (code "131") (name "unconnected-(U8-U-Pad10)") (class "Default")
      (node (ref "U8") (pin "10") (pinfunction "U_10") (pintype "passive+no_connect"))
    )
    (net (code "132") (name "unconnected-(U8-V-Pad9)") (class "Default")
      (node (ref "U8") (pin "9") (pinfunction "V_9") (pintype "passive+no_connect"))
    )
    (net (code "133") (name "unconnected-(U8-W{slash}PWM-Pad8)") (class "Default")
      (node (ref "U8") (pin "8") (pinfunction "W/PWM_8") (pintype "passive+no_connect"))
    )
    (net (code "134") (name "unconnected-(U9-NC-Pad4)") (class "Default")
      (node (ref "U9") (pin "4") (pinfunction "NC_4") (pintype "passive+no_connect"))
    )
    (net (code "135") (name "unconnected-(USBC1-CC1-PadA5)") (class "Default")
      (node (ref "USBC1") (pin "A5") (pinfunction "CC1_A5") (pintype "passive+no_connect"))
    )
    (net (code "136") (name "unconnected-(USBC1-CC2-PadB5)") (class "Default")
      (node (ref "USBC1") (pin "B5") (pinfunction "CC2_B5") (pintype "passive+no_connect"))
    )
    (net (code "137") (name "unconnected-(USBC1-SBU1-PadA8)") (class "Default")
      (node (ref "USBC1") (pin "A8") (pinfunction "SBU1_A8") (pintype "passive+no_connect"))
    )
    (net (code "138") (name "unconnected-(USBC1-SBU2-PadB8)") (class "Default")
      (node (ref "USBC1") (pin "B8") (pinfunction "SBU2_B8") (pintype "passive+no_connect"))
    )
    (net (code "139") (name "unconnected-(X1-EN-Pad1)") (class "Default")
      (node (ref "X1") (pin "1") (pinfunction "EN_1") (pintype "passive+no_connect"))
    )
  )
)
